# ProPrj_OrcaSDVX.net
KiCad netlist of a schematic drawn in EasyEDA Pro
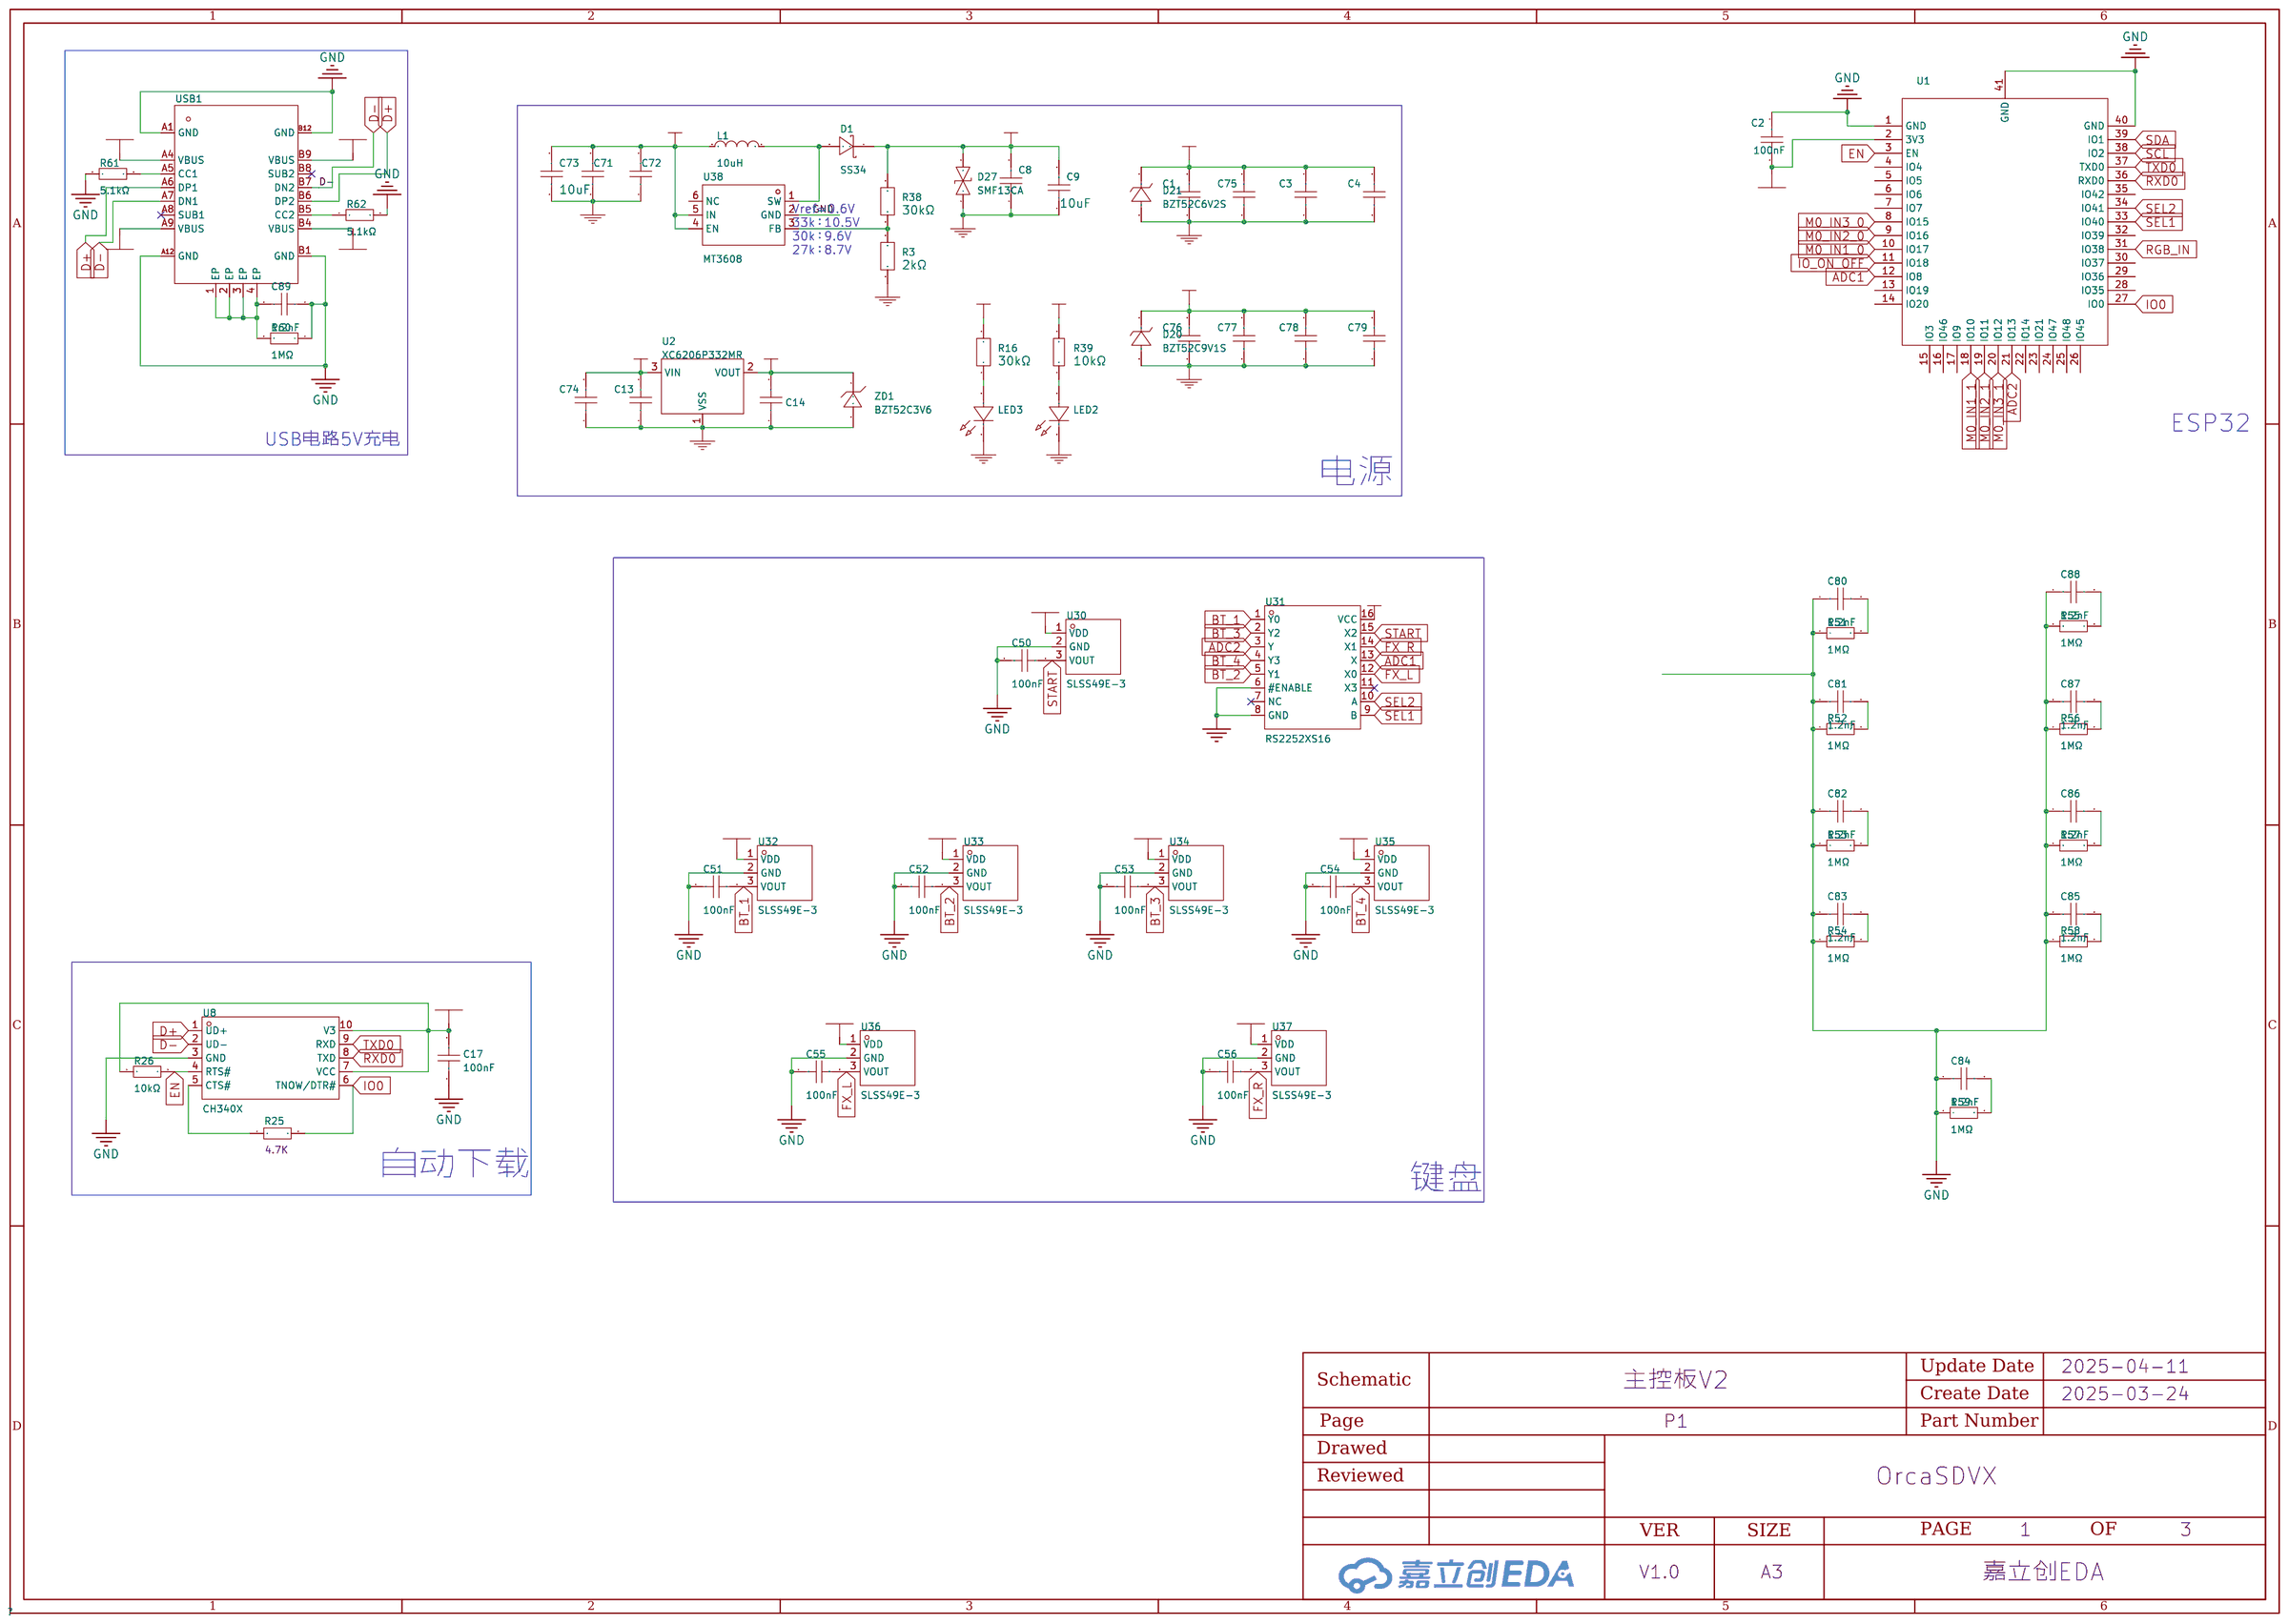
[diagram p0: P1]
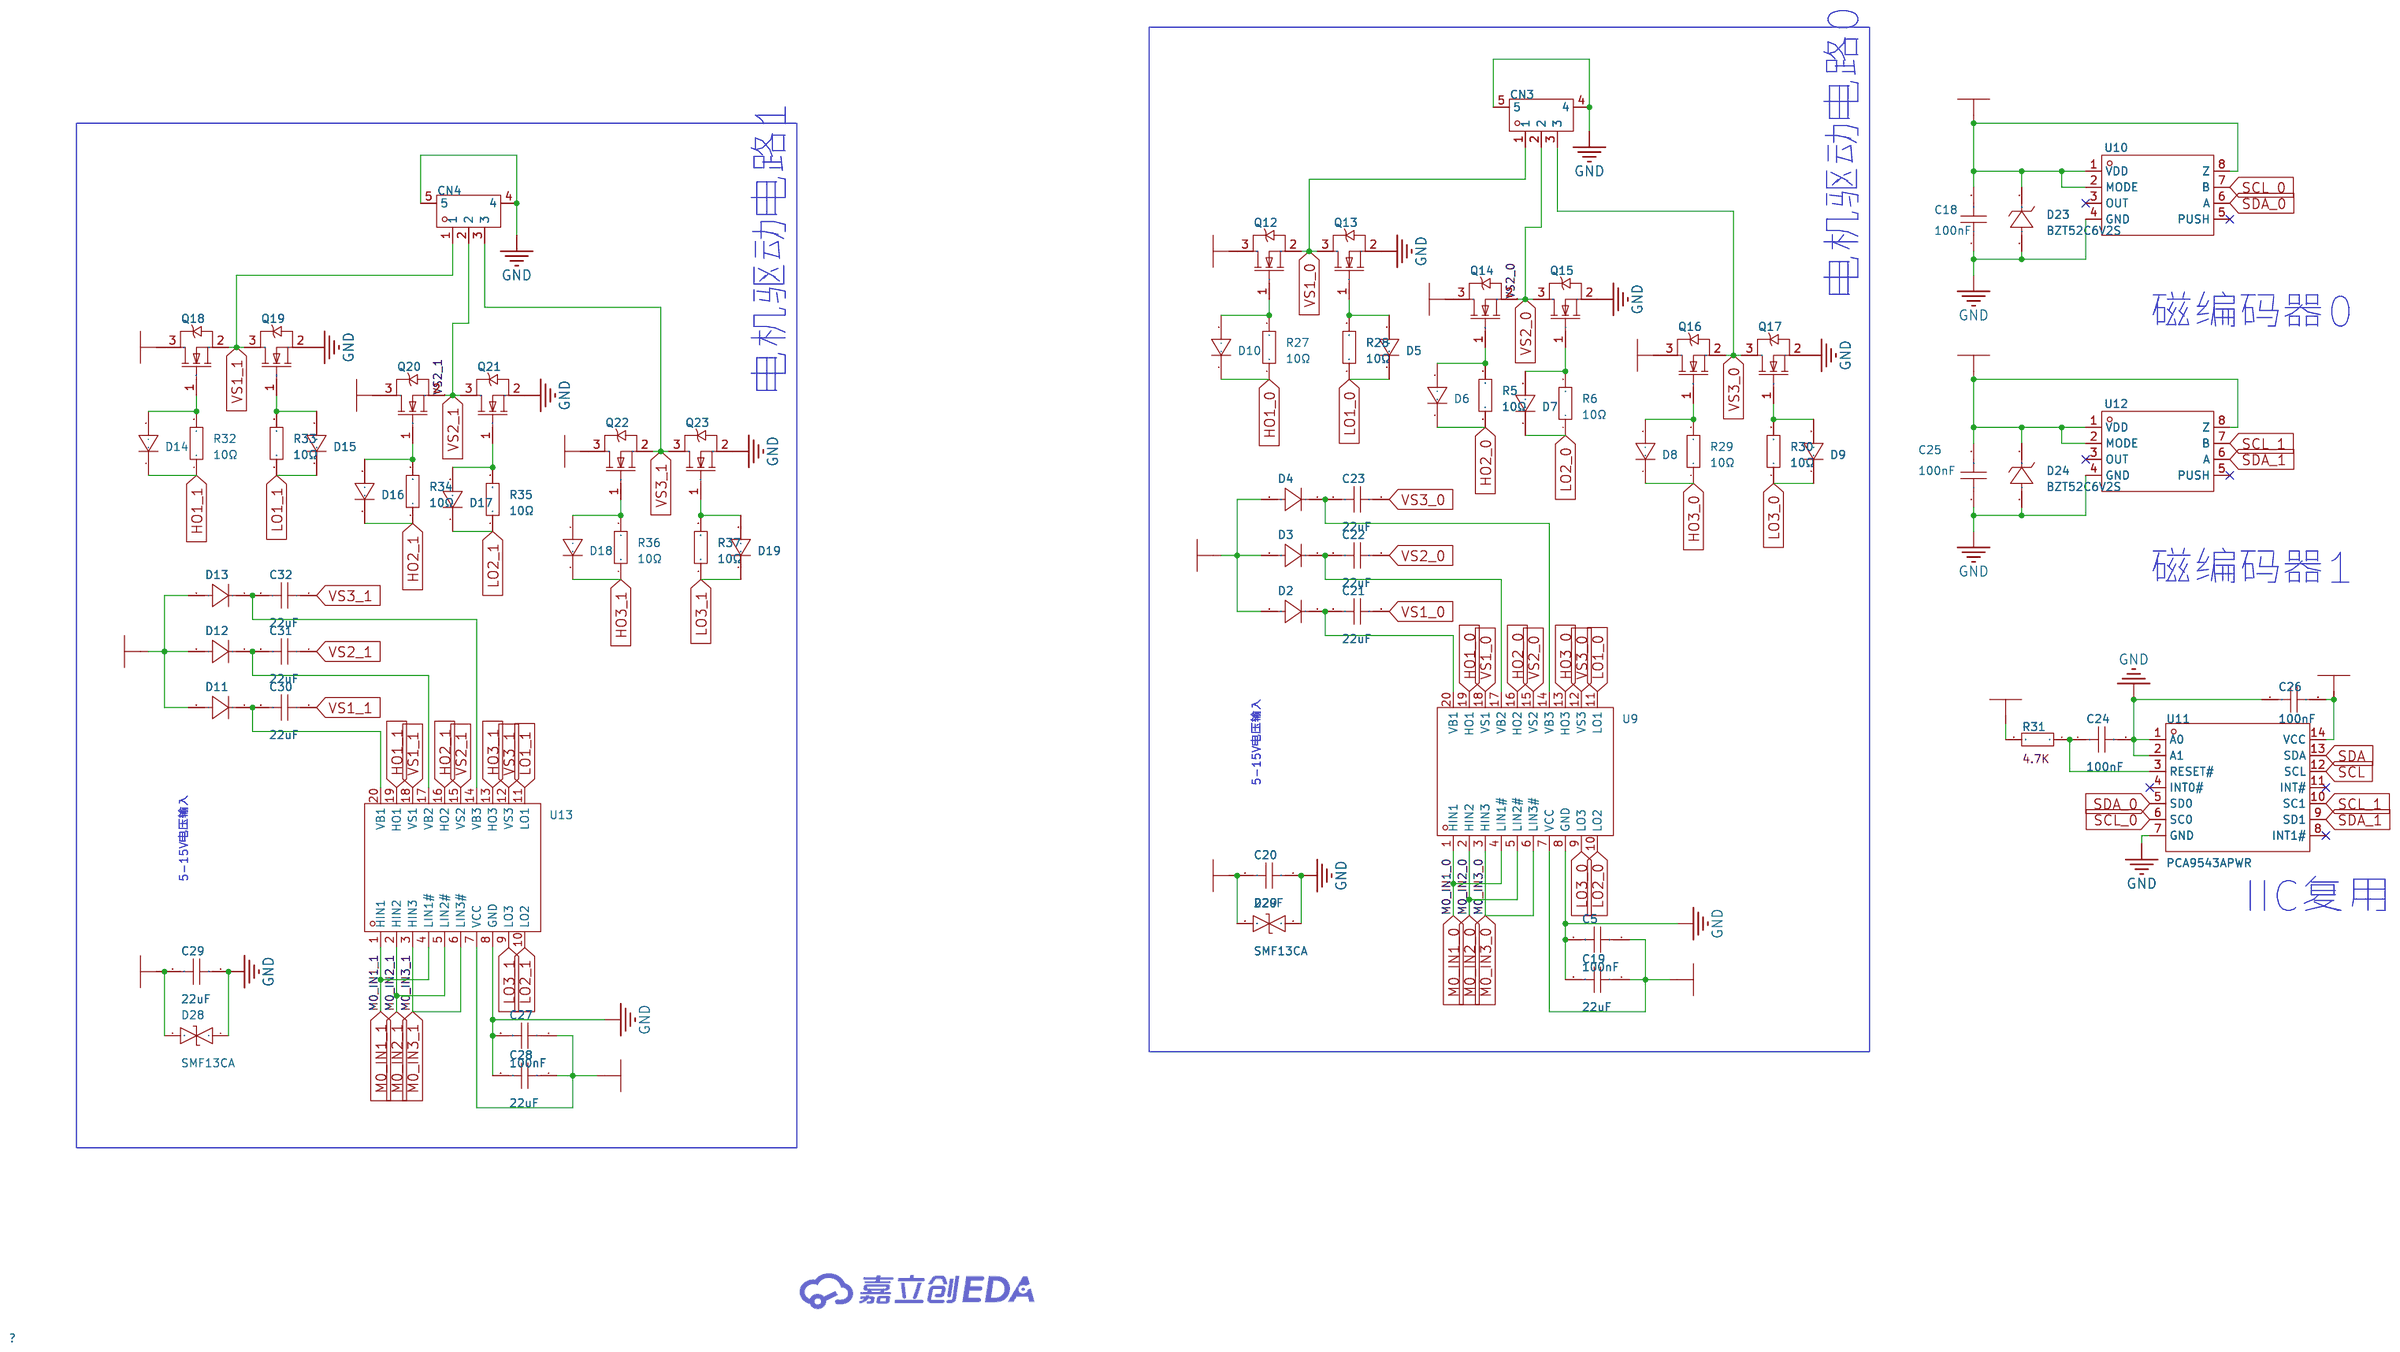
[diagram p1: 电机驱动电路]
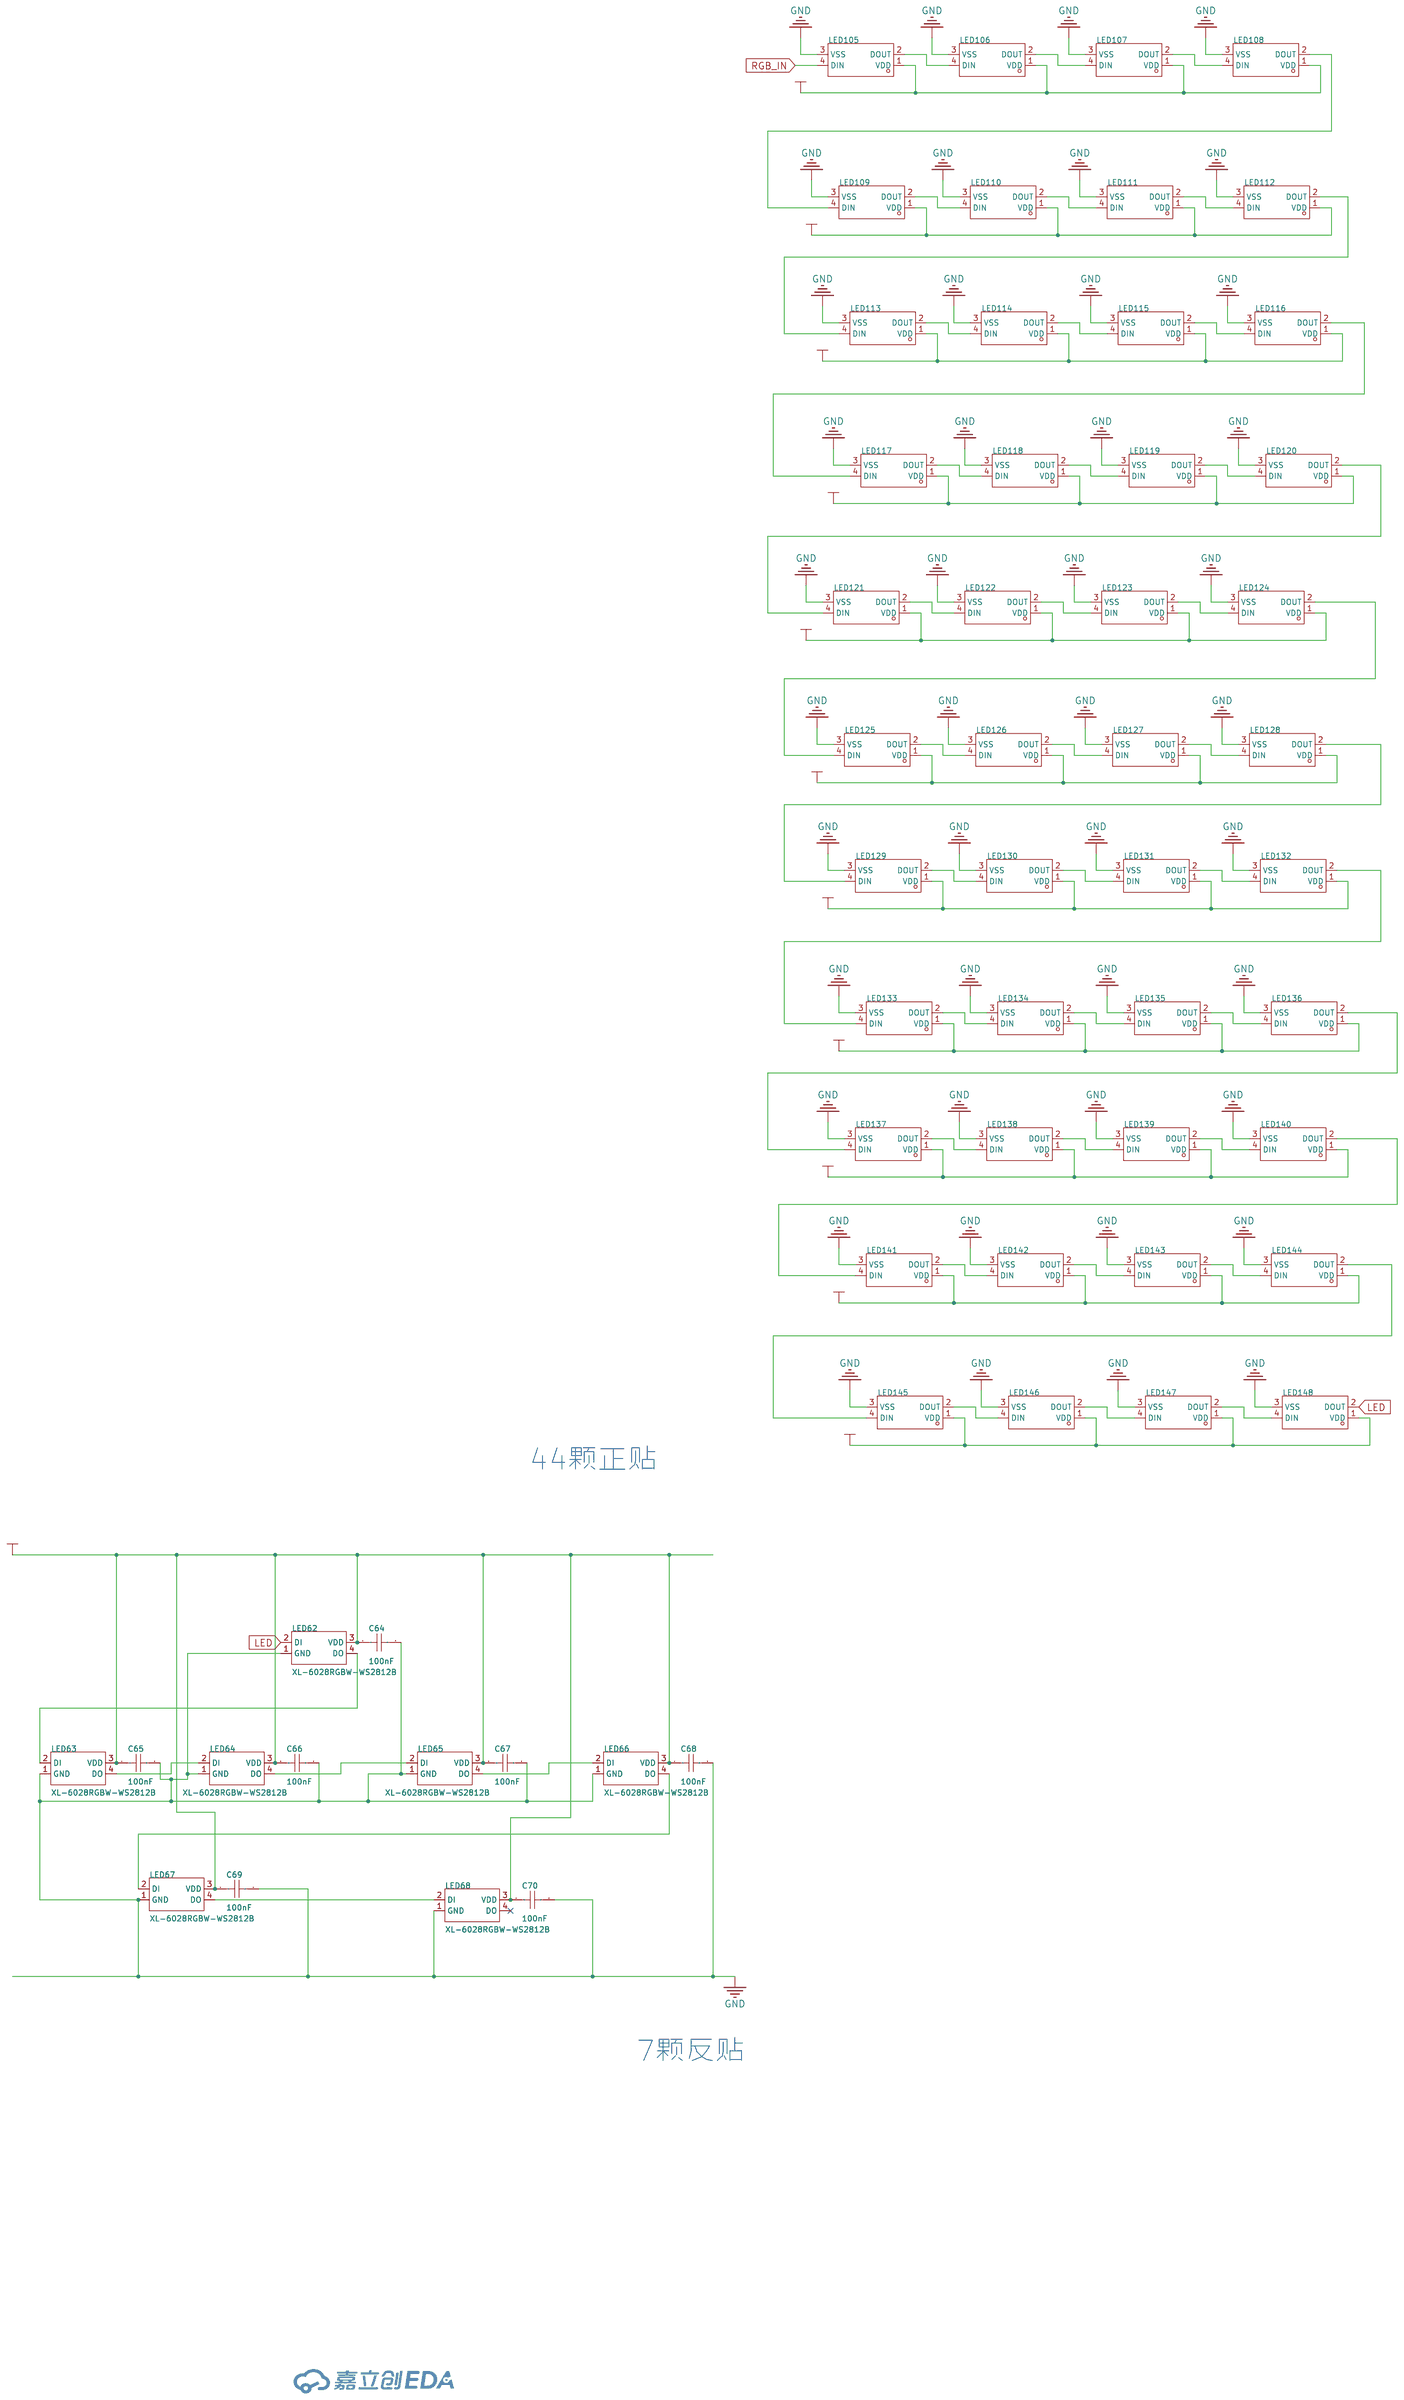
[diagram p2: 灯]

(export (version "E")
  (design (tool "Eeschema 10.0.6"))
  (components
    (comp (ref "C1") (value "100nF") (libsource (lib "easyedapro") (part "CC0603KRX7R9BB104")))
    (comp (ref "C2")
      (value "100nF")
      (footprint "easyedapro:C0603")
      (description "容值:100nF;精度:±10%;额定电压:50V;温度系数:X7R;")
      (fields
        (field (name "Manufacturer Part") "CC0603KRX7R9BB104")
        (field (name "Manufacturer") "YAGEO(国巨)")
      )
      (libsource (lib "") (part "CC0603KRX7R9BB104_1"))
    )
    (comp (ref "C3") (value "100nF") (libsource (lib "easyedapro") (part "CC0603KRX7R9BB104")))
    (comp (ref "C4") (value "100nF") (libsource (lib "easyedapro") (part "CC0603KRX7R9BB104")))
    (comp (ref "C8") (value "100nF") (libsource (lib "easyedapro") (part "CC0603KRX7R9BB104")))
    (comp (ref "C9") (value "10uF") (libsource (lib "easyedapro") (part "CL21A106KAYNNNE")))
    (comp (ref "C13") (value "100nF") (libsource (lib "easyedapro") (part "CC0603KRX7R9BB104")))
    (comp (ref "C14") (value "100nF") (libsource (lib "easyedapro") (part "CC0603KRX7R9BB104")))
    (comp (ref "C17")
      (value "100nF")
      (footprint "easyedapro:C0603")
      (description "容值:100nF;精度:±10%;额定电压:50V;温度系数:X7R;")
      (fields
        (field (name "Manufacturer Part") "CC0603KRX7R9BB104")
        (field (name "Manufacturer") "YAGEO(国巨)")
      )
      (libsource (lib "") (part "CC0603KRX7R9BB104_1"))
    )
    (comp (ref "C50")
      (value "100nF")
      (footprint "easyedapro:C0603")
      (description "容值:100nF;精度:±10%;额定电压:50V;温度系数:X7R;")
      (fields
        (field (name "Manufacturer Part") "CGA0603X7R104K500JT")
        (field (name "Manufacturer") "HRE(芯声)")
      )
      (libsource (lib "easyedapro") (part "CGA0603X7R104K500JT"))
    )
    (comp (ref "C51")
      (value "100nF")
      (footprint "easyedapro:C0603")
      (description "容值:100nF;精度:±10%;额定电压:50V;温度系数:X7R;")
      (fields
        (field (name "Manufacturer Part") "CGA0603X7R104K500JT")
        (field (name "Manufacturer") "HRE(芯声)")
      )
      (libsource (lib "easyedapro") (part "CGA0603X7R104K500JT"))
    )
    (comp (ref "C52")
      (value "100nF")
      (footprint "easyedapro:C0603")
      (description "容值:100nF;精度:±10%;额定电压:50V;温度系数:X7R;")
      (fields
        (field (name "Manufacturer Part") "CGA0603X7R104K500JT")
        (field (name "Manufacturer") "HRE(芯声)")
      )
      (libsource (lib "easyedapro") (part "CGA0603X7R104K500JT"))
    )
    (comp (ref "C53")
      (value "100nF")
      (footprint "easyedapro:C0603")
      (description "容值:100nF;精度:±10%;额定电压:50V;温度系数:X7R;")
      (fields
        (field (name "Manufacturer Part") "CGA0603X7R104K500JT")
        (field (name "Manufacturer") "HRE(芯声)")
      )
      (libsource (lib "easyedapro") (part "CGA0603X7R104K500JT"))
    )
    (comp (ref "C54")
      (value "100nF")
      (footprint "easyedapro:C0603")
      (description "容值:100nF;精度:±10%;额定电压:50V;温度系数:X7R;")
      (fields
        (field (name "Manufacturer Part") "CGA0603X7R104K500JT")
        (field (name "Manufacturer") "HRE(芯声)")
      )
      (libsource (lib "easyedapro") (part "CGA0603X7R104K500JT"))
    )
    (comp (ref "C55")
      (value "100nF")
      (footprint "easyedapro:C0603")
      (description "容值:100nF;精度:±10%;额定电压:50V;温度系数:X7R;")
      (fields
        (field (name "Manufacturer Part") "CGA0603X7R104K500JT")
        (field (name "Manufacturer") "HRE(芯声)")
      )
      (libsource (lib "easyedapro") (part "CGA0603X7R104K500JT"))
    )
    (comp (ref "C56")
      (value "100nF")
      (footprint "easyedapro:C0603")
      (description "容值:100nF;精度:±10%;额定电压:50V;温度系数:X7R;")
      (fields
        (field (name "Manufacturer Part") "CGA0603X7R104K500JT")
        (field (name "Manufacturer") "HRE(芯声)")
      )
      (libsource (lib "easyedapro") (part "CGA0603X7R104K500JT"))
    )
    (comp (ref "C71") (value "100nF") (libsource (lib "easyedapro") (part "CC0603KRX7R9BB104")))
    (comp (ref "C72") (value "100nF") (libsource (lib "easyedapro") (part "CC0603KRX7R9BB104")))
    (comp (ref "C73")
      (value "10uF")
      (fields
        (field (name "Manufacturer Part") "CL10A106MA8NRNC")
        (field (name "Manufacturer") "SAMSUNG(三星)")
      )
      (libsource (lib "easyedapro") (part "CL21A106KAYNNNE"))
    )
    (comp (ref "C74") (value "100nF") (libsource (lib "easyedapro") (part "CC0603KRX7R9BB104")))
    (comp (ref "C75") (value "100nF") (libsource (lib "easyedapro") (part "CC0603KRX7R9BB104")))
    (comp (ref "C76") (value "100nF") (libsource (lib "easyedapro") (part "CC0603KRX7R9BB104")))
    (comp (ref "C77") (value "100nF") (libsource (lib "easyedapro") (part "CC0603KRX7R9BB104")))
    (comp (ref "C78") (value "100nF") (libsource (lib "easyedapro") (part "CC0603KRX7R9BB104")))
    (comp (ref "C79") (value "100nF") (libsource (lib "easyedapro") (part "CC0603KRX7R9BB104")))
    (comp (ref "C80")
      (value "1.2nF")
      (footprint "easyedapro:C1210")
      (description "容值:1.2nF;精度:±5%;额定电压:1kV;温度系数:C0G;")
      (fields (field (name "Manufacturer Part") "FV32N122J102EEG") (field (name "Manufacturer") "PSA(信昌电陶)"))
      (libsource (lib "easyedapro") (part "FV32N122J102EEG"))
    )
    (comp (ref "C81")
      (value "1.2nF")
      (footprint "easyedapro:C1210")
      (description "容值:1.2nF;精度:±5%;额定电压:1kV;温度系数:C0G;")
      (fields (field (name "Manufacturer Part") "FV32N122J102EEG") (field (name "Manufacturer") "PSA(信昌电陶)"))
      (libsource (lib "easyedapro") (part "FV32N122J102EEG"))
    )
    (comp (ref "C82")
      (value "1.2nF")
      (footprint "easyedapro:C1210")
      (description "容值:1.2nF;精度:±5%;额定电压:1kV;温度系数:C0G;")
      (fields (field (name "Manufacturer Part") "FV32N122J102EEG") (field (name "Manufacturer") "PSA(信昌电陶)"))
      (libsource (lib "easyedapro") (part "FV32N122J102EEG"))
    )
    (comp (ref "C83")
      (value "1.2nF")
      (footprint "easyedapro:C1210")
      (description "容值:1.2nF;精度:±5%;额定电压:1kV;温度系数:C0G;")
      (fields (field (name "Manufacturer Part") "FV32N122J102EEG") (field (name "Manufacturer") "PSA(信昌电陶)"))
      (libsource (lib "easyedapro") (part "FV32N122J102EEG"))
    )
    (comp (ref "C84")
      (value "1.2nF")
      (footprint "easyedapro:C1210")
      (description "容值:1.2nF;精度:±5%;额定电压:1kV;温度系数:C0G;")
      (fields (field (name "Manufacturer Part") "FV32N122J102EEG") (field (name "Manufacturer") "PSA(信昌电陶)"))
      (libsource (lib "easyedapro") (part "FV32N122J102EEG"))
    )
    (comp (ref "C85")
      (value "1.2nF")
      (footprint "easyedapro:C1210")
      (description "容值:1.2nF;精度:±5%;额定电压:1kV;温度系数:C0G;")
      (fields (field (name "Manufacturer Part") "FV32N122J102EEG") (field (name "Manufacturer") "PSA(信昌电陶)"))
      (libsource (lib "easyedapro") (part "FV32N122J102EEG"))
    )
    (comp (ref "C86")
      (value "1.2nF")
      (footprint "easyedapro:C1210")
      (description "容值:1.2nF;精度:±5%;额定电压:1kV;温度系数:C0G;")
      (fields (field (name "Manufacturer Part") "FV32N122J102EEG") (field (name "Manufacturer") "PSA(信昌电陶)"))
      (libsource (lib "easyedapro") (part "FV32N122J102EEG"))
    )
    (comp (ref "C87")
      (value "1.2nF")
      (footprint "easyedapro:C1210")
      (description "容值:1.2nF;精度:±5%;额定电压:1kV;温度系数:C0G;")
      (fields (field (name "Manufacturer Part") "FV32N122J102EEG") (field (name "Manufacturer") "PSA(信昌电陶)"))
      (libsource (lib "easyedapro") (part "FV32N122J102EEG"))
    )
    (comp (ref "C88")
      (value "1.2nF")
      (footprint "easyedapro:C1210")
      (description "容值:1.2nF;精度:±5%;额定电压:1kV;温度系数:C0G;")
      (fields (field (name "Manufacturer Part") "FV32N122J102EEG") (field (name "Manufacturer") "PSA(信昌电陶)"))
      (libsource (lib "easyedapro") (part "FV32N122J102EEG"))
    )
    (comp (ref "C89")
      (value "1.2nF")
      (footprint "easyedapro:C1210")
      (description "容值:1.2nF;精度:±5%;额定电压:1kV;温度系数:C0G;")
      (fields (field (name "Manufacturer Part") "FV32N122J102EEG") (field (name "Manufacturer") "PSA(信昌电陶)"))
      (libsource (lib "easyedapro") (part "FV32N122J102EEG"))
    )
    (comp (ref "D1")
      (value "SS34")
      (footprint "easyedapro:SMA_L4.3-W2.6-LS5.2-RD")
      (description "二极管配置:独立式;正向压降(Vf):550mV@3A;直流反向耐压(Vr):40V;整流电流:3A;")
      (fields (field (name "Manufacturer") "MDD(辰达半导体)"))
      (libsource (lib "easyedapro") (part "SS34_C8678"))
    )
    (comp (ref "D20")
      (value "BZT52C9V1S")
      (footprint "easyedapro:SOD-323_L1.7-W1.3-LS2.6-RD")
      (description "二极管配置:独立式;稳压值(标称值):9.1V;稳压值(范围):8.5V~9.6V;耗散功率(Pd):200mW;")
      (fields (field (name "Manufacturer") "宏嘉诚"))
      (libsource (lib "easyedapro") (part "BZT52C9V1S_C19077445"))
    )
    (comp (ref "D21")
      (value "BZT52C6V2S")
      (footprint "easyedapro:SOD-323_L1.7-W1.3-LS2.6-RD")
      (description "二极管配置:独立式;稳压值(标称值):6.2V;稳压值(范围):5.8V~6.2V;功率(Pd):200mW;")
      (fields (field (name "Manufacturer") "宏迦橙"))
      (libsource (lib "easyedapro") (part "BZT52C6V2S_C19077442"))
    )
    (comp (ref "D27")
      (value "SMF13CA")
      (footprint "easyedapro:SOD-123_L2.8-W1.8-LS3.7-BI-1")
      (description "极性:双向;反向截止电压(Vrwm):13V;钳位电压:21.5V;峰值脉冲电流(Ipp):9.3A;峰值脉冲功率(Ppp):200W;击穿电压:14.4V;")
      (fields (field (name "Manufacturer") "ElecSuper(静芯微)"))
      (libsource (lib "easyedapro") (part "SMF13CA_C5693166"))
    )
    (comp (ref "L1")
      (value "10uH")
      (footprint "easyedapro:IND-SMD_L3.0-W3.0_FTC303020D")
      (description "电感值:10uH;精度:±20%;额定电流:2.5A;饱和电流(Isat):3.8A;类型:一体成型电感;")
      (fields
        (field (name "Manufacturer Part") "FTC303020D100MBCA")
        (field (name "Manufacturer") "cjiang(长江微电)")
      )
      (libsource (lib "easyedapro") (part "FTC303020D100MBCA"))
    )
    (comp (ref "LED2") (value "XL-1608UGC-04") (libsource (lib "easyedapro") (part "XL-1608PGC-06")))
    (comp (ref "LED3") (value "XL-1608UGC-04") (libsource (lib "easyedapro") (part "XL-1608PGC-06")))
    (comp (ref "R3")
      (value "2kΩ")
      (fields (field (name "Manufacturer") "UNI-ROYAL(厚声)"))
      (libsource (lib "easyedapro") (part "1k"))
    )
    (comp (ref "R16")
      (value "30kΩ")
      (fields (field (name "Manufacturer") "UNI-ROYAL(厚声)"))
      (libsource (lib "easyedapro") (part "1k"))
    )
    (comp (ref "R25")
      (value "~")
      (footprint "easyedapro:R0603")
      (description "4.7K")
      (fields
        (field (name "Manufacturer Part") "0603WAF4701T5E")
        (field (name "Manufacturer") "UNI-ROYAL(厚声)")
      )
      (libsource (lib "easyedapro") (part "0603WAF4701T5E"))
    )
    (comp (ref "R26")
      (value "10kΩ")
      (footprint "easyedapro:R0603")
      (description "电阻类型:厚膜电阻;阻值:10kΩ;精度:±1%;功率:1/10W;温度系数:±100ppm/;最大工作电压:75V;工作温度范围:-55~+155;")
      (fields
        (field (name "Manufacturer Part") "0603WAF1002T5E")
        (field (name "Manufacturer") "UNI-ROYAL(厚声)")
      )
      (libsource (lib "easyedapro") (part "0603WAF1002T5E"))
    )
    (comp (ref "R38")
      (value "30kΩ")
      (fields (field (name "Manufacturer") "UNI-ROYAL(厚声)"))
      (libsource (lib "easyedapro") (part "1k"))
    )
    (comp (ref "R39")
      (value "10kΩ")
      (fields (field (name "Manufacturer") "YAGEO(国巨)"))
      (libsource (lib "easyedapro") (part "RC0603FR-0710KL"))
    )
    (comp (ref "R51")
      (value "1MΩ")
      (footprint "easyedapro:R2512")
      (description "电阻类型:厚膜电阻;阻值:1MΩ;精度:±1%;功率:1W;最大工作电压:800V;")
      (fields
        (field (name "Manufacturer Part") "HR2512F1M00E04Z")
        (field (name "Manufacturer") "EVER OHMS(天二科技)")
      )
      (libsource (lib "easyedapro") (part "HR2512F1ME04"))
    )
    (comp (ref "R52")
      (value "1MΩ")
      (footprint "easyedapro:R2512")
      (description "电阻类型:厚膜电阻;阻值:1MΩ;精度:±1%;功率:1W;最大工作电压:800V;")
      (fields
        (field (name "Manufacturer Part") "HR2512F1M00E04Z")
        (field (name "Manufacturer") "EVER OHMS(天二科技)")
      )
      (libsource (lib "easyedapro") (part "HR2512F1ME04"))
    )
    (comp (ref "R53")
      (value "1MΩ")
      (footprint "easyedapro:R2512")
      (description "电阻类型:厚膜电阻;阻值:1MΩ;精度:±1%;功率:1W;最大工作电压:800V;")
      (fields
        (field (name "Manufacturer Part") "HR2512F1M00E04Z")
        (field (name "Manufacturer") "EVER OHMS(天二科技)")
      )
      (libsource (lib "easyedapro") (part "HR2512F1ME04"))
    )
    (comp (ref "R54")
      (value "1MΩ")
      (footprint "easyedapro:R2512")
      (description "电阻类型:厚膜电阻;阻值:1MΩ;精度:±1%;功率:1W;最大工作电压:800V;")
      (fields
        (field (name "Manufacturer Part") "HR2512F1M00E04Z")
        (field (name "Manufacturer") "EVER OHMS(天二科技)")
      )
      (libsource (lib "easyedapro") (part "HR2512F1ME04"))
    )
    (comp (ref "R55")
      (value "1MΩ")
      (footprint "easyedapro:R2512")
      (description "电阻类型:厚膜电阻;阻值:1MΩ;精度:±1%;功率:1W;最大工作电压:800V;")
      (fields
        (field (name "Manufacturer Part") "HR2512F1M00E04Z")
        (field (name "Manufacturer") "EVER OHMS(天二科技)")
      )
      (libsource (lib "easyedapro") (part "HR2512F1ME04"))
    )
    (comp (ref "R56")
      (value "1MΩ")
      (footprint "easyedapro:R2512")
      (description "电阻类型:厚膜电阻;阻值:1MΩ;精度:±1%;功率:1W;最大工作电压:800V;")
      (fields
        (field (name "Manufacturer Part") "HR2512F1M00E04Z")
        (field (name "Manufacturer") "EVER OHMS(天二科技)")
      )
      (libsource (lib "easyedapro") (part "HR2512F1ME04"))
    )
    (comp (ref "R57")
      (value "1MΩ")
      (footprint "easyedapro:R2512")
      (description "电阻类型:厚膜电阻;阻值:1MΩ;精度:±1%;功率:1W;最大工作电压:800V;")
      (fields
        (field (name "Manufacturer Part") "HR2512F1M00E04Z")
        (field (name "Manufacturer") "EVER OHMS(天二科技)")
      )
      (libsource (lib "easyedapro") (part "HR2512F1ME04"))
    )
    (comp (ref "R58")
      (value "1MΩ")
      (footprint "easyedapro:R2512")
      (description "电阻类型:厚膜电阻;阻值:1MΩ;精度:±1%;功率:1W;最大工作电压:800V;")
      (fields
        (field (name "Manufacturer Part") "HR2512F1M00E04Z")
        (field (name "Manufacturer") "EVER OHMS(天二科技)")
      )
      (libsource (lib "easyedapro") (part "HR2512F1ME04"))
    )
    (comp (ref "R59")
      (value "1MΩ")
      (footprint "easyedapro:R2512")
      (description "电阻类型:厚膜电阻;阻值:1MΩ;精度:±1%;功率:1W;最大工作电压:800V;")
      (fields
        (field (name "Manufacturer Part") "HR2512F1M00E04Z")
        (field (name "Manufacturer") "EVER OHMS(天二科技)")
      )
      (libsource (lib "easyedapro") (part "HR2512F1ME04"))
    )
    (comp (ref "R60")
      (value "1MΩ")
      (footprint "easyedapro:R2512")
      (description "电阻类型:厚膜电阻;阻值:1MΩ;精度:±1%;功率:1W;最大工作电压:800V;")
      (fields
        (field (name "Manufacturer Part") "HR2512F1M00E04Z")
        (field (name "Manufacturer") "EVER OHMS(天二科技)")
      )
      (libsource (lib "easyedapro") (part "HR2512F1ME04"))
    )
    (comp (ref "R61")
      (value "5.1kΩ")
      (footprint "easyedapro:R0603")
      (description "电阻类型:厚膜电阻;阻值:5.1kΩ;精度:±1%;功率:100mW;最大工作电压:75V;温度系数:±100ppm/°C;")
      (fields
        (field (name "Manufacturer Part") "0603WAF5101T5E")
        (field (name "Manufacturer") "UNI-ROYAL(厚声)")
      )
      (libsource (lib "easyedapro") (part "0603WAF5101T5E"))
    )
    (comp (ref "R62")
      (value "5.1kΩ")
      (footprint "easyedapro:R0603")
      (description "电阻类型:厚膜电阻;阻值:5.1kΩ;精度:±1%;功率:100mW;最大工作电压:75V;温度系数:±100ppm/°C;")
      (fields
        (field (name "Manufacturer Part") "0603WAF5101T5E")
        (field (name "Manufacturer") "UNI-ROYAL(厚声)")
      )
      (libsource (lib "easyedapro") (part "0603WAF5101T5E"))
    )
    (comp (ref "U1")
      (value "ESP32-S3-WROOM-1U-N16R8")
      (footprint "easyedapro:WIRELM-SMD_ESP32-S3-WROOM-1U")
      (fields (field (name "Manufacturer") "ESPRESSIF(乐鑫)"))
      (libsource (lib "easyedapro") (part "ESP32-S3-WROOM-1U-N8"))
    )
    (comp (ref "U2")
      (value "XC6206P332MR")
      (footprint "easyedapro:SOT-23-3_L2.9-W1.3-P1.90-LS2.4-BR")
      (description "输出类型:固定;最大输入电压:8V;输出电压:3.3V;最大输出电流:300mA;输出极性:正极;")
      (fields (field (name "Manufacturer") "HXY MOSFET(华轩阳电子)"))
      (libsource (lib "easyedapro") (part "XC6206P332MR_C5148692"))
    )
    (comp (ref "U8")
      (value "CH340X")
      (footprint "easyedapro:MSOP-10_L3.0-W3.0-P0.50-LS5.0-BL")
      (fields (field (name "Manufacturer") "WCH(南京沁恒)"))
      (libsource (lib "easyedapro") (part "CH340X"))
    )
    (comp (ref "U30")
      (value "SLSS49E-3")
      (footprint "easyedapro:SOT-23-3_L2.9-W1.6-P1.90-LS2.8-BR-CW")
      (fields (field (name "Manufacturer") "Slkor(萨科微)"))
      (libsource (lib "easyedapro") (part "SLSS49E-3"))
    )
    (comp (ref "U31")
      (value "RS2252XS16")
      (footprint "easyedapro:SOIC-16_L9.9-W3.9-P1.27-LS6.0-BL")
      (description "2通道4选1复用器")
      (fields (field (name "Manufacturer") "RUNIC(润石)"))
      (libsource (lib "easyedapro") (part "RS2252XS16"))
    )
    (comp (ref "U32")
      (value "SLSS49E-3")
      (footprint "easyedapro:SOT-23-3_L2.9-W1.6-P1.90-LS2.8-BR-CW")
      (fields (field (name "Manufacturer") "Slkor(萨科微)"))
      (libsource (lib "easyedapro") (part "SLSS49E-3"))
    )
    (comp (ref "U33")
      (value "SLSS49E-3")
      (footprint "easyedapro:SOT-23-3_L2.9-W1.6-P1.90-LS2.8-BR-CW")
      (fields (field (name "Manufacturer") "Slkor(萨科微)"))
      (libsource (lib "easyedapro") (part "SLSS49E-3"))
    )
    (comp (ref "U34")
      (value "SLSS49E-3")
      (footprint "easyedapro:SOT-23-3_L2.9-W1.6-P1.90-LS2.8-BR-CW")
      (fields (field (name "Manufacturer") "Slkor(萨科微)"))
      (libsource (lib "easyedapro") (part "SLSS49E-3"))
    )
    (comp (ref "U35")
      (value "SLSS49E-3")
      (footprint "easyedapro:SOT-23-3_L2.9-W1.6-P1.90-LS2.8-BR-CW")
      (fields (field (name "Manufacturer") "Slkor(萨科微)"))
      (libsource (lib "easyedapro") (part "SLSS49E-3"))
    )
    (comp (ref "U36")
      (value "SLSS49E-3")
      (footprint "easyedapro:SOT-23-3_L2.9-W1.6-P1.90-LS2.8-BR-CW")
      (fields (field (name "Manufacturer") "Slkor(萨科微)"))
      (libsource (lib "easyedapro") (part "SLSS49E-3"))
    )
    (comp (ref "U37")
      (value "SLSS49E-3")
      (footprint "easyedapro:SOT-23-3_L2.9-W1.6-P1.90-LS2.8-BR-CW")
      (fields (field (name "Manufacturer") "Slkor(萨科微)"))
      (libsource (lib "easyedapro") (part "SLSS49E-3"))
    )
    (comp (ref "U38")
      (value "MT3608")
      (footprint "easyedapro:SOT-23-6_L2.9-W1.6-P0.95-LS2.8-BL")
      (description "功能类型:升压型;输入电压:2V~24V;输出电压:28V;输出电流(最大值):-;")
      (fields (field (name "Manufacturer") "西安航天民芯"))
      (libsource (lib "easyedapro") (part "MT3608"))
    )
    (comp (ref "USB1")
      (value "~")
      (footprint "easyedapro:USB-C-SMD_KH-TYPE-C-16P")
      (description "连接器类型:Type-C;标准:-;公母:母座;触点数量:16;端口数量:1;安装方式:卧贴;额定电流 - 电源:3A;工作温度范围:-40~+85;")
      (fields
        (field (name "Manufacturer Part") "KH-TYPE-C-16P")
        (field (name "Manufacturer") "kinghelm(金航标)")
      )
      (libsource (lib "easyedapro") (part "KH-TYPE-C-16P"))
    )
    (comp (ref "ZD1")
      (value "BZT52C3V6")
      (footprint "easyedapro:SOD-123_L2.8-W1.8-LS3.7-RD")
      (description "二极管配置:独立式;稳压值(标称值):3.6V;稳压值(范围):3.4V~3.8V;功率:350mW;精度:-;")
      (fields (field (name "Manufacturer") "CJ(江苏长电/长晶)"))
      (libsource (lib "easyedapro") (part "BZT52C3V6_C2113"))
    )
    (comp (ref "C5")
      (value "100nF")
      (footprint "easyedapro:C0603")
      (description "容值:100nF;精度:±10%;额定电压:50V;温度系数:X7R;")
      (fields
        (field (name "Manufacturer Part") "CC0603KRX7R9BB104")
        (field (name "Manufacturer") "YAGEO(国巨)")
      )
      (libsource (lib "easyedapro") (part "CC0603KRX7R9BB104"))
    )
    (comp (ref "C18")
      (value "100nF")
      (footprint "easyedapro:C0603")
      (description "容值:100nF;精度:±10%;额定电压:50V;温度系数:X7R;")
      (fields
        (field (name "Manufacturer Part") "CC0603KRX7R9BB104")
        (field (name "Manufacturer") "YAGEO(国巨)")
      )
      (libsource (lib "easyedapro") (part "CC0603KRX7R9BB104"))
    )
    (comp (ref "C19")
      (value "22uF")
      (footprint "easyedapro:C0805")
      (description "容值:22uF;精度:±20%;额定电压:25V;温度系数:X5R;")
      (fields
        (field (name "Manufacturer Part") "CL21A226MAQNNNE")
        (field (name "Manufacturer") "SAMSUNG(三星)")
      )
      (libsource (lib "easyedapro") (part "CL21A226MAQNNNE"))
    )
    (comp (ref "C20")
      (value "22uF")
      (footprint "easyedapro:C0805")
      (description "容值:22uF;精度:±20%;额定电压:25V;温度系数:X5R;")
      (fields
        (field (name "Manufacturer Part") "CL21A226MAQNNNE")
        (field (name "Manufacturer") "SAMSUNG(三星)")
      )
      (libsource (lib "easyedapro") (part "CL21A226MAQNNNE"))
    )
    (comp (ref "C21")
      (value "22uF")
      (footprint "easyedapro:C0805")
      (description "容值:22uF;精度:±20%;额定电压:25V;温度系数:X5R;")
      (fields
        (field (name "Manufacturer Part") "CL21A226MAQNNNE")
        (field (name "Manufacturer") "SAMSUNG(三星)")
      )
      (libsource (lib "easyedapro") (part "CL21A226MAQNNNE"))
    )
    (comp (ref "C22")
      (value "22uF")
      (footprint "easyedapro:C0805")
      (description "容值:22uF;精度:±20%;额定电压:25V;温度系数:X5R;")
      (fields
        (field (name "Manufacturer Part") "CL21A226MAQNNNE")
        (field (name "Manufacturer") "SAMSUNG(三星)")
      )
      (libsource (lib "easyedapro") (part "CL21A226MAQNNNE"))
    )
    (comp (ref "C23")
      (value "22uF")
      (footprint "easyedapro:C0805")
      (description "容值:22uF;精度:±20%;额定电压:25V;温度系数:X5R;")
      (fields
        (field (name "Manufacturer Part") "CL21A226MAQNNNE")
        (field (name "Manufacturer") "SAMSUNG(三星)")
      )
      (libsource (lib "easyedapro") (part "CL21A226MAQNNNE"))
    )
    (comp (ref "C24")
      (value "100nF")
      (footprint "easyedapro:C0603")
      (description "容值:100nF;精度:±10%;额定电压:50V;温度系数:X7R;")
      (fields
        (field (name "Manufacturer Part") "CC0603KRX7R9BB104")
        (field (name "Manufacturer") "YAGEO(国巨)")
      )
      (libsource (lib "easyedapro") (part "CC0603KRX7R9BB104"))
    )
    (comp (ref "C25")
      (value "100nF")
      (footprint "easyedapro:C0603")
      (description "容值:100nF;精度:±10%;额定电压:50V;温度系数:X7R;")
      (fields
        (field (name "Manufacturer Part") "CC0603KRX7R9BB104")
        (field (name "Manufacturer") "YAGEO(国巨)")
      )
      (libsource (lib "easyedapro") (part "CC0603KRX7R9BB104"))
    )
    (comp (ref "C26")
      (value "100nF")
      (footprint "easyedapro:C0603")
      (description "容值:100nF;精度:±10%;额定电压:50V;温度系数:X7R;")
      (fields
        (field (name "Manufacturer Part") "CC0603KRX7R9BB104")
        (field (name "Manufacturer") "YAGEO(国巨)")
      )
      (libsource (lib "easyedapro") (part "CC0603KRX7R9BB104"))
    )
    (comp (ref "C27")
      (value "100nF")
      (footprint "easyedapro:C0603")
      (description "容值:100nF;精度:±10%;额定电压:50V;温度系数:X7R;")
      (fields
        (field (name "Manufacturer Part") "CC0603KRX7R9BB104")
        (field (name "Manufacturer") "YAGEO(国巨)")
      )
      (libsource (lib "easyedapro") (part "CC0603KRX7R9BB104"))
    )
    (comp (ref "C28")
      (value "22uF")
      (footprint "easyedapro:C0805")
      (description "容值:22uF;精度:±20%;额定电压:25V;温度系数:X5R;")
      (fields
        (field (name "Manufacturer Part") "CL21A226MAQNNNE")
        (field (name "Manufacturer") "SAMSUNG(三星)")
      )
      (libsource (lib "easyedapro") (part "CL21A226MAQNNNE"))
    )
    (comp (ref "C29")
      (value "22uF")
      (footprint "easyedapro:C0805")
      (description "容值:22uF;精度:±20%;额定电压:25V;温度系数:X5R;")
      (fields
        (field (name "Manufacturer Part") "CL21A226MAQNNNE")
        (field (name "Manufacturer") "SAMSUNG(三星)")
      )
      (libsource (lib "easyedapro") (part "CL21A226MAQNNNE"))
    )
    (comp (ref "C30")
      (value "22uF")
      (footprint "easyedapro:C0805")
      (description "容值:22uF;精度:±20%;额定电压:25V;温度系数:X5R;")
      (fields
        (field (name "Manufacturer Part") "CL21A226MAQNNNE")
        (field (name "Manufacturer") "SAMSUNG(三星)")
      )
      (libsource (lib "easyedapro") (part "CL21A226MAQNNNE"))
    )
    (comp (ref "C31")
      (value "22uF")
      (footprint "easyedapro:C0805")
      (description "容值:22uF;精度:±20%;额定电压:25V;温度系数:X5R;")
      (fields
        (field (name "Manufacturer Part") "CL21A226MAQNNNE")
        (field (name "Manufacturer") "SAMSUNG(三星)")
      )
      (libsource (lib "easyedapro") (part "CL21A226MAQNNNE"))
    )
    (comp (ref "C32")
      (value "22uF")
      (footprint "easyedapro:C0805")
      (description "容值:22uF;精度:±20%;额定电压:25V;温度系数:X5R;")
      (fields
        (field (name "Manufacturer Part") "CL21A226MAQNNNE")
        (field (name "Manufacturer") "SAMSUNG(三星)")
      )
      (libsource (lib "easyedapro") (part "CL21A226MAQNNNE"))
    )
    (comp (ref "CN3")
      (value "~")
      (footprint "easyedapro:CONN-SMD_X0800WRS-03HF-LPV01")
      (description "参考系列:-;间距:0.8mm;插针结构:1x3P;排数:1;每排PIN数:3;行距:-;公母:公型插针;安装方式:卧贴;额定电流:500mA;工作温度范围:-25~+85;")
      (fields
        (field (name "Manufacturer Part") "X0800WRS-03HF-LPV01")
        (field (name "Manufacturer") "XKBConnectivity(中国星坤)")
      )
      (libsource (lib "easyedapro") (part "X0800WRS-03HF-LPV01"))
    )
    (comp (ref "CN4")
      (value "~")
      (footprint "easyedapro:CONN-SMD_X0800WRS-03HF-LPV01")
      (description "参考系列:-;间距:0.8mm;插针结构:1x3P;排数:1;每排PIN数:3;行距:-;公母:公型插针;安装方式:卧贴;额定电流:500mA;工作温度范围:-25~+85;")
      (fields
        (field (name "Manufacturer Part") "X0800WRS-03HF-LPV01")
        (field (name "Manufacturer") "XKBConnectivity(中国星坤)")
      )
      (libsource (lib "easyedapro") (part "X0800WRS-03HF-LPV01"))
    )
    (comp (ref "D2")
      (value "~")
      (footprint "easyedapro:SOD-123FL_L2.7-W1.8-LS3.8-RD")
      (fields (field (name "Manufacturer Part") "FR107") (field (name "Manufacturer") "Slkor(萨科微)"))
      (libsource (lib "easyedapro") (part "FR107_C2760867"))
    )
    (comp (ref "D3")
      (value "~")
      (footprint "easyedapro:SOD-123FL_L2.7-W1.8-LS3.8-RD")
      (fields (field (name "Manufacturer Part") "FR107") (field (name "Manufacturer") "Slkor(萨科微)"))
      (libsource (lib "easyedapro") (part "FR107_C2760867"))
    )
    (comp (ref "D4")
      (value "~")
      (footprint "easyedapro:SOD-123FL_L2.7-W1.8-LS3.8-RD")
      (fields (field (name "Manufacturer Part") "FR107") (field (name "Manufacturer") "Slkor(萨科微)"))
      (libsource (lib "easyedapro") (part "FR107_C2760867"))
    )
    (comp (ref "D5")
      (value "~")
      (footprint "easyedapro:SOD-123F_L2.7-W1.6-LS3.8-RD")
      (fields (field (name "Manufacturer Part") "1N4148W") (field (name "Manufacturer") "ST(先科)"))
      (libsource (lib "easyedapro") (part "1N4148W_C81598"))
    )
    (comp (ref "D6")
      (value "~")
      (footprint "easyedapro:SOD-123F_L2.7-W1.6-LS3.8-RD")
      (fields (field (name "Manufacturer Part") "1N4148W") (field (name "Manufacturer") "ST(先科)"))
      (libsource (lib "easyedapro") (part "1N4148W_C81598"))
    )
    (comp (ref "D7")
      (value "~")
      (footprint "easyedapro:SOD-123F_L2.7-W1.6-LS3.8-RD")
      (fields (field (name "Manufacturer Part") "1N4148W") (field (name "Manufacturer") "ST(先科)"))
      (libsource (lib "easyedapro") (part "1N4148W_C81598"))
    )
    (comp (ref "D8")
      (value "~")
      (footprint "easyedapro:SOD-123F_L2.7-W1.6-LS3.8-RD")
      (fields (field (name "Manufacturer Part") "1N4148W") (field (name "Manufacturer") "ST(先科)"))
      (libsource (lib "easyedapro") (part "1N4148W_C81598"))
    )
    (comp (ref "D9")
      (value "~")
      (footprint "easyedapro:SOD-123F_L2.7-W1.6-LS3.8-RD")
      (fields (field (name "Manufacturer Part") "1N4148W") (field (name "Manufacturer") "ST(先科)"))
      (libsource (lib "easyedapro") (part "1N4148W_C81598"))
    )
    (comp (ref "D10")
      (value "~")
      (footprint "easyedapro:SOD-123F_L2.7-W1.6-LS3.8-RD")
      (fields (field (name "Manufacturer Part") "1N4148W") (field (name "Manufacturer") "ST(先科)"))
      (libsource (lib "easyedapro") (part "1N4148W_C81598"))
    )
    (comp (ref "D11")
      (value "~")
      (footprint "easyedapro:SOD-123FL_L2.7-W1.8-LS3.8-RD")
      (fields (field (name "Manufacturer Part") "FR107") (field (name "Manufacturer") "Slkor(萨科微)"))
      (libsource (lib "easyedapro") (part "FR107_C2760867"))
    )
    (comp (ref "D12")
      (value "~")
      (footprint "easyedapro:SOD-123FL_L2.7-W1.8-LS3.8-RD")
      (fields (field (name "Manufacturer Part") "FR107") (field (name "Manufacturer") "Slkor(萨科微)"))
      (libsource (lib "easyedapro") (part "FR107_C2760867"))
    )
    (comp (ref "D13")
      (value "~")
      (footprint "easyedapro:SOD-123FL_L2.7-W1.8-LS3.8-RD")
      (fields (field (name "Manufacturer Part") "FR107") (field (name "Manufacturer") "Slkor(萨科微)"))
      (libsource (lib "easyedapro") (part "FR107_C2760867"))
    )
    (comp (ref "D14")
      (value "~")
      (footprint "easyedapro:SOD-123F_L2.7-W1.6-LS3.8-RD")
      (fields (field (name "Manufacturer Part") "1N4148W") (field (name "Manufacturer") "ST(先科)"))
      (libsource (lib "easyedapro") (part "1N4148W_C81598"))
    )
    (comp (ref "D15")
      (value "~")
      (footprint "easyedapro:SOD-123F_L2.7-W1.6-LS3.8-RD")
      (fields (field (name "Manufacturer Part") "1N4148W") (field (name "Manufacturer") "ST(先科)"))
      (libsource (lib "easyedapro") (part "1N4148W_C81598"))
    )
    (comp (ref "D16")
      (value "~")
      (footprint "easyedapro:SOD-123F_L2.7-W1.6-LS3.8-RD")
      (fields (field (name "Manufacturer Part") "1N4148W") (field (name "Manufacturer") "ST(先科)"))
      (libsource (lib "easyedapro") (part "1N4148W_C81598"))
    )
    (comp (ref "D17")
      (value "~")
      (footprint "easyedapro:SOD-123F_L2.7-W1.6-LS3.8-RD")
      (fields (field (name "Manufacturer Part") "1N4148W") (field (name "Manufacturer") "ST(先科)"))
      (libsource (lib "easyedapro") (part "1N4148W_C81598"))
    )
    (comp (ref "D18")
      (value "~")
      (footprint "easyedapro:SOD-123F_L2.7-W1.6-LS3.8-RD")
      (fields (field (name "Manufacturer Part") "1N4148W") (field (name "Manufacturer") "ST(先科)"))
      (libsource (lib "easyedapro") (part "1N4148W_C81598"))
    )
    (comp (ref "D19")
      (value "~")
      (footprint "easyedapro:SOD-123F_L2.7-W1.6-LS3.8-RD")
      (fields (field (name "Manufacturer Part") "1N4148W") (field (name "Manufacturer") "ST(先科)"))
      (libsource (lib "easyedapro") (part "1N4148W_C81598"))
    )
    (comp (ref "D23")
      (value "BZT52C6V2S")
      (footprint "easyedapro:SOD-323_L1.7-W1.3-LS2.6-RD")
      (description "二极管配置:独立式;稳压值(标称值):6.2V;稳压值(范围):5.8V~6.2V;功率(Pd):200mW;")
      (fields (field (name "Manufacturer") "宏迦橙"))
      (libsource (lib "easyedapro") (part "BZT52C6V2S_C19077442"))
    )
    (comp (ref "D24")
      (value "BZT52C6V2S")
      (footprint "easyedapro:SOD-323_L1.7-W1.3-LS2.6-RD")
      (description "二极管配置:独立式;稳压值(标称值):6.2V;稳压值(范围):5.8V~6.2V;功率(Pd):200mW;")
      (fields (field (name "Manufacturer") "宏迦橙"))
      (libsource (lib "easyedapro") (part "BZT52C6V2S_C19077442"))
    )
    (comp (ref "D28")
      (value "SMF13CA")
      (footprint "easyedapro:SOD-123_L2.8-W1.8-LS3.7-BI-1")
      (description "极性:双向;反向截止电压(Vrwm):13V;钳位电压:21.5V;峰值脉冲电流(Ipp):9.3A;峰值脉冲功率(Ppp):200W;击穿电压:14.4V;")
      (fields (field (name "Manufacturer") "ElecSuper(静芯微)"))
      (libsource (lib "easyedapro") (part "SMF13CA_C5693166"))
    )
    (comp (ref "D29")
      (value "SMF13CA")
      (footprint "easyedapro:SOD-123_L2.8-W1.8-LS3.7-BI-1")
      (description "极性:双向;反向截止电压(Vrwm):13V;钳位电压:21.5V;峰值脉冲电流(Ipp):9.3A;峰值脉冲功率(Ppp):200W;击穿电压:14.4V;")
      (fields (field (name "Manufacturer") "ElecSuper(静芯微)"))
      (libsource (lib "easyedapro") (part "SMF13CA_C5693166"))
    )
    (comp (ref "Q12")
      (value "~")
      (footprint "easyedapro:SOT-23-3_L2.9-W1.3-P0.95-LS2.4-BR")
      (fields (field (name "Manufacturer Part") "AP2300") (field (name "Manufacturer") "ALLPOWER(铨力)"))
      (libsource (lib "easyedapro") (part "AP2300"))
    )
    (comp (ref "Q13")
      (value "~")
      (footprint "easyedapro:SOT-23-3_L2.9-W1.3-P0.95-LS2.4-BR")
      (fields (field (name "Manufacturer Part") "AP2300") (field (name "Manufacturer") "ALLPOWER(铨力)"))
      (libsource (lib "easyedapro") (part "AP2300"))
    )
    (comp (ref "Q14")
      (value "~")
      (footprint "easyedapro:SOT-23-3_L2.9-W1.3-P0.95-LS2.4-BR")
      (fields (field (name "Manufacturer Part") "AP2300") (field (name "Manufacturer") "ALLPOWER(铨力)"))
      (libsource (lib "easyedapro") (part "AP2300"))
    )
    (comp (ref "Q15")
      (value "~")
      (footprint "easyedapro:SOT-23-3_L2.9-W1.3-P0.95-LS2.4-BR")
      (fields (field (name "Manufacturer Part") "AP2300") (field (name "Manufacturer") "ALLPOWER(铨力)"))
      (libsource (lib "easyedapro") (part "AP2300"))
    )
    (comp (ref "Q16")
      (value "~")
      (footprint "easyedapro:SOT-23-3_L2.9-W1.3-P0.95-LS2.4-BR")
      (fields (field (name "Manufacturer Part") "AP2300") (field (name "Manufacturer") "ALLPOWER(铨力)"))
      (libsource (lib "easyedapro") (part "AP2300"))
    )
    (comp (ref "Q17")
      (value "~")
      (footprint "easyedapro:SOT-23-3_L2.9-W1.3-P0.95-LS2.4-BR")
      (fields (field (name "Manufacturer Part") "AP2300") (field (name "Manufacturer") "ALLPOWER(铨力)"))
      (libsource (lib "easyedapro") (part "AP2300"))
    )
    (comp (ref "Q18")
      (value "~")
      (footprint "easyedapro:SOT-23-3_L2.9-W1.3-P0.95-LS2.4-BR")
      (fields (field (name "Manufacturer Part") "AP2300") (field (name "Manufacturer") "ALLPOWER(铨力)"))
      (libsource (lib "easyedapro") (part "AP2300"))
    )
    (comp (ref "Q19")
      (value "~")
      (footprint "easyedapro:SOT-23-3_L2.9-W1.3-P0.95-LS2.4-BR")
      (fields (field (name "Manufacturer Part") "AP2300") (field (name "Manufacturer") "ALLPOWER(铨力)"))
      (libsource (lib "easyedapro") (part "AP2300"))
    )
    (comp (ref "Q20")
      (value "~")
      (footprint "easyedapro:SOT-23-3_L2.9-W1.3-P0.95-LS2.4-BR")
      (fields (field (name "Manufacturer Part") "AP2300") (field (name "Manufacturer") "ALLPOWER(铨力)"))
      (libsource (lib "easyedapro") (part "AP2300"))
    )
    (comp (ref "Q21")
      (value "~")
      (footprint "easyedapro:SOT-23-3_L2.9-W1.3-P0.95-LS2.4-BR")
      (fields (field (name "Manufacturer Part") "AP2300") (field (name "Manufacturer") "ALLPOWER(铨力)"))
      (libsource (lib "easyedapro") (part "AP2300"))
    )
    (comp (ref "Q22")
      (value "~")
      (footprint "easyedapro:SOT-23-3_L2.9-W1.3-P0.95-LS2.4-BR")
      (fields (field (name "Manufacturer Part") "AP2300") (field (name "Manufacturer") "ALLPOWER(铨力)"))
      (libsource (lib "easyedapro") (part "AP2300"))
    )
    (comp (ref "Q23")
      (value "~")
      (footprint "easyedapro:SOT-23-3_L2.9-W1.3-P0.95-LS2.4-BR")
      (fields (field (name "Manufacturer Part") "AP2300") (field (name "Manufacturer") "ALLPOWER(铨力)"))
      (libsource (lib "easyedapro") (part "AP2300"))
    )
    (comp (ref "R5")
      (value "10Ω")
      (footprint "easyedapro:R0603")
      (description "电阻类型:厚膜电阻;阻值:10Ω;精度:±1%;功率:1/10W;温度系数:±400ppm/;最大工作电压:75V;工作温度范围:-55~+155;")
      (fields
        (field (name "Manufacturer Part") "0603WAF100JT5E")
        (field (name "Manufacturer") "UNI-ROYAL(厚声)")
      )
      (libsource (lib "easyedapro") (part "0603WAF100JT5E"))
    )
    (comp (ref "R6")
      (value "10Ω")
      (footprint "easyedapro:R0603")
      (description "电阻类型:厚膜电阻;阻值:10Ω;精度:±1%;功率:1/10W;温度系数:±400ppm/;最大工作电压:75V;工作温度范围:-55~+155;")
      (fields
        (field (name "Manufacturer Part") "0603WAF100JT5E")
        (field (name "Manufacturer") "UNI-ROYAL(厚声)")
      )
      (libsource (lib "easyedapro") (part "0603WAF100JT5E"))
    )
    (comp (ref "R27")
      (value "10Ω")
      (footprint "easyedapro:R0603")
      (description "电阻类型:厚膜电阻;阻值:10Ω;精度:±1%;功率:1/10W;温度系数:±400ppm/;最大工作电压:75V;工作温度范围:-55~+155;")
      (fields
        (field (name "Manufacturer Part") "0603WAF100JT5E")
        (field (name "Manufacturer") "UNI-ROYAL(厚声)")
      )
      (libsource (lib "easyedapro") (part "0603WAF100JT5E"))
    )
    (comp (ref "R28")
      (value "10Ω")
      (footprint "easyedapro:R0603")
      (description "电阻类型:厚膜电阻;阻值:10Ω;精度:±1%;功率:1/10W;温度系数:±400ppm/;最大工作电压:75V;工作温度范围:-55~+155;")
      (fields
        (field (name "Manufacturer Part") "0603WAF100JT5E")
        (field (name "Manufacturer") "UNI-ROYAL(厚声)")
      )
      (libsource (lib "easyedapro") (part "0603WAF100JT5E"))
    )
    (comp (ref "R29")
      (value "10Ω")
      (footprint "easyedapro:R0603")
      (description "电阻类型:厚膜电阻;阻值:10Ω;精度:±1%;功率:1/10W;温度系数:±400ppm/;最大工作电压:75V;工作温度范围:-55~+155;")
      (fields
        (field (name "Manufacturer Part") "0603WAF100JT5E")
        (field (name "Manufacturer") "UNI-ROYAL(厚声)")
      )
      (libsource (lib "easyedapro") (part "0603WAF100JT5E"))
    )
    (comp (ref "R30")
      (value "10Ω")
      (footprint "easyedapro:R0603")
      (description "电阻类型:厚膜电阻;阻值:10Ω;精度:±1%;功率:1/10W;温度系数:±400ppm/;最大工作电压:75V;工作温度范围:-55~+155;")
      (fields
        (field (name "Manufacturer Part") "0603WAF100JT5E")
        (field (name "Manufacturer") "UNI-ROYAL(厚声)")
      )
      (libsource (lib "easyedapro") (part "0603WAF100JT5E"))
    )
    (comp (ref "R31")
      (value "~")
      (footprint "easyedapro:R0603")
      (description "4.7K")
      (fields
        (field (name "Manufacturer Part") "0603WAF4701T5E")
        (field (name "Manufacturer") "UNI-ROYAL(厚声)")
      )
      (libsource (lib "easyedapro") (part "0603WAF4701T5E"))
    )
    (comp (ref "R32")
      (value "10Ω")
      (footprint "easyedapro:R0603")
      (description "电阻类型:厚膜电阻;阻值:10Ω;精度:±1%;功率:1/10W;温度系数:±400ppm/;最大工作电压:75V;工作温度范围:-55~+155;")
      (fields
        (field (name "Manufacturer Part") "0603WAF100JT5E")
        (field (name "Manufacturer") "UNI-ROYAL(厚声)")
      )
      (libsource (lib "easyedapro") (part "0603WAF100JT5E"))
    )
    (comp (ref "R33")
      (value "10Ω")
      (footprint "easyedapro:R0603")
      (description "电阻类型:厚膜电阻;阻值:10Ω;精度:±1%;功率:1/10W;温度系数:±400ppm/;最大工作电压:75V;工作温度范围:-55~+155;")
      (fields
        (field (name "Manufacturer Part") "0603WAF100JT5E")
        (field (name "Manufacturer") "UNI-ROYAL(厚声)")
      )
      (libsource (lib "easyedapro") (part "0603WAF100JT5E"))
    )
    (comp (ref "R34")
      (value "10Ω")
      (footprint "easyedapro:R0603")
      (description "电阻类型:厚膜电阻;阻值:10Ω;精度:±1%;功率:1/10W;温度系数:±400ppm/;最大工作电压:75V;工作温度范围:-55~+155;")
      (fields
        (field (name "Manufacturer Part") "0603WAF100JT5E")
        (field (name "Manufacturer") "UNI-ROYAL(厚声)")
      )
      (libsource (lib "easyedapro") (part "0603WAF100JT5E"))
    )
    (comp (ref "R35")
      (value "10Ω")
      (footprint "easyedapro:R0603")
      (description "电阻类型:厚膜电阻;阻值:10Ω;精度:±1%;功率:1/10W;温度系数:±400ppm/;最大工作电压:75V;工作温度范围:-55~+155;")
      (fields
        (field (name "Manufacturer Part") "0603WAF100JT5E")
        (field (name "Manufacturer") "UNI-ROYAL(厚声)")
      )
      (libsource (lib "easyedapro") (part "0603WAF100JT5E"))
    )
    (comp (ref "R36")
      (value "10Ω")
      (footprint "easyedapro:R0603")
      (description "电阻类型:厚膜电阻;阻值:10Ω;精度:±1%;功率:1/10W;温度系数:±400ppm/;最大工作电压:75V;工作温度范围:-55~+155;")
      (fields
        (field (name "Manufacturer Part") "0603WAF100JT5E")
        (field (name "Manufacturer") "UNI-ROYAL(厚声)")
      )
      (libsource (lib "easyedapro") (part "0603WAF100JT5E"))
    )
    (comp (ref "R37")
      (value "10Ω")
      (footprint "easyedapro:R0603")
      (description "电阻类型:厚膜电阻;阻值:10Ω;精度:±1%;功率:1/10W;温度系数:±400ppm/;最大工作电压:75V;工作温度范围:-55~+155;")
      (fields
        (field (name "Manufacturer Part") "0603WAF100JT5E")
        (field (name "Manufacturer") "UNI-ROYAL(厚声)")
      )
      (libsource (lib "easyedapro") (part "0603WAF100JT5E"))
    )
    (comp (ref "U9")
      (value "~")
      (footprint "easyedapro:TSSOP-20_L6.5-W4.4-P0.65-LS6.4-BL")
      (description "EG2133是一款高性价比的三相半桥驱动芯片，配合六颗Nmos可以组成三相直流无刷电机驱动器。包装为管装。")
      (fields (field (name "Manufacturer Part") "EG2133") (field (name "Manufacturer") "EG(屹晶微)"))
      (libsource (lib "easyedapro") (part "EG2133"))
    )
    (comp (ref "U10")
      (value "~")
      (footprint "easyedapro:SOP-8_L4.9-W3.9-P1.27-LS6.0-BL")
      (description "磁性编码器 磁性编码开关 磁性角度检测IC 可编程磁性角度位置芯片")
      (fields (field (name "Manufacturer Part") "MT6701CT-STD") (field (name "Manufacturer") "MagnTek(麦歌恩)"))
      (libsource (lib "easyedapro") (part "MT6701CT-STD"))
    )
    (comp (ref "U11")
      (value "PCA9543APWR")
      (footprint "easyedapro:TSSOP-14_L5.0-W4.4-P0.65-LS6.4-BL")
      (description "PCA9543A 具有中断、复位和电压转换功能的 2 通道 2.3V 至 5.5V I2C/SMBus 开关")
      (fields (field (name "Manufacturer") "TI(德州仪器)"))
      (libsource (lib "easyedapro") (part "PCA9543APWR"))
    )
    (comp (ref "U12")
      (value "~")
      (footprint "easyedapro:SOP-8_L4.9-W3.9-P1.27-LS6.0-BL")
      (description "磁性编码器 磁性编码开关 磁性角度检测IC 可编程磁性角度位置芯片")
      (fields (field (name "Manufacturer Part") "MT6701CT-STD") (field (name "Manufacturer") "MagnTek(麦歌恩)"))
      (libsource (lib "easyedapro") (part "MT6701CT-STD"))
    )
    (comp (ref "U13")
      (value "~")
      (footprint "easyedapro:TSSOP-20_L6.5-W4.4-P0.65-LS6.4-BL")
      (description "EG2133是一款高性价比的三相半桥驱动芯片，配合六颗Nmos可以组成三相直流无刷电机驱动器。包装为管装。")
      (fields (field (name "Manufacturer Part") "EG2133") (field (name "Manufacturer") "EG(屹晶微)"))
      (libsource (lib "easyedapro") (part "EG2133"))
    )
    (comp (ref "C64")
      (value "100nF")
      (footprint "easyedapro:C0603")
      (description "容值:100nF;精度:±10%;额定电压:50V;温度系数:X7R;")
      (fields
        (field (name "Manufacturer Part") "CGA0603X7R104K500JT")
        (field (name "Manufacturer") "HRE(芯声)")
      )
      (libsource (lib "easyedapro") (part "CGA0603X7R104K500JT"))
    )
    (comp (ref "C65")
      (value "100nF")
      (footprint "easyedapro:C0603")
      (description "容值:100nF;精度:±10%;额定电压:50V;温度系数:X7R;")
      (fields
        (field (name "Manufacturer Part") "CGA0603X7R104K500JT")
        (field (name "Manufacturer") "HRE(芯声)")
      )
      (libsource (lib "easyedapro") (part "CGA0603X7R104K500JT"))
    )
    (comp (ref "C66")
      (value "100nF")
      (footprint "easyedapro:C0603")
      (description "容值:100nF;精度:±10%;额定电压:50V;温度系数:X7R;")
      (fields
        (field (name "Manufacturer Part") "CGA0603X7R104K500JT")
        (field (name "Manufacturer") "HRE(芯声)")
      )
      (libsource (lib "easyedapro") (part "CGA0603X7R104K500JT"))
    )
    (comp (ref "C67")
      (value "100nF")
      (footprint "easyedapro:C0603")
      (description "容值:100nF;精度:±10%;额定电压:50V;温度系数:X7R;")
      (fields
        (field (name "Manufacturer Part") "CGA0603X7R104K500JT")
        (field (name "Manufacturer") "HRE(芯声)")
      )
      (libsource (lib "easyedapro") (part "CGA0603X7R104K500JT"))
    )
    (comp (ref "C68")
      (value "100nF")
      (footprint "easyedapro:C0603")
      (description "容值:100nF;精度:±10%;额定电压:50V;温度系数:X7R;")
      (fields
        (field (name "Manufacturer Part") "CGA0603X7R104K500JT")
        (field (name "Manufacturer") "HRE(芯声)")
      )
      (libsource (lib "easyedapro") (part "CGA0603X7R104K500JT"))
    )
    (comp (ref "C69")
      (value "100nF")
      (footprint "easyedapro:C0603")
      (description "容值:100nF;精度:±10%;额定电压:50V;温度系数:X7R;")
      (fields
        (field (name "Manufacturer Part") "CGA0603X7R104K500JT")
        (field (name "Manufacturer") "HRE(芯声)")
      )
      (libsource (lib "easyedapro") (part "CGA0603X7R104K500JT"))
    )
    (comp (ref "C70")
      (value "100nF")
      (footprint "easyedapro:C0603")
      (description "容值:100nF;精度:±10%;额定电压:50V;温度系数:X7R;")
      (fields
        (field (name "Manufacturer Part") "CGA0603X7R104K500JT")
        (field (name "Manufacturer") "HRE(芯声)")
      )
      (libsource (lib "easyedapro") (part "CGA0603X7R104K500JT"))
    )
    (comp (ref "LED62")
      (value "XL-6028RGBW-WS2812B")
      (footprint "easyedapro:LED-SMD_4P-L3.2-W2.8-XL-6028RGBW-WS2812B")
      (description "6028幻彩雾状（ws2812b)")
      (fields (field (name "Manufacturer") "XINGLIGHT(成兴光)"))
      (libsource (lib "easyedapro") (part "XL-6028RGBW-WS2812B"))
    )
    (comp (ref "LED63")
      (value "XL-6028RGBW-WS2812B")
      (footprint "easyedapro:LED-SMD_4P-L3.2-W2.8-XL-6028RGBW-WS2812B")
      (description "6028幻彩雾状（ws2812b)")
      (fields (field (name "Manufacturer") "XINGLIGHT(成兴光)"))
      (libsource (lib "easyedapro") (part "XL-6028RGBW-WS2812B"))
    )
    (comp (ref "LED64")
      (value "XL-6028RGBW-WS2812B")
      (footprint "easyedapro:LED-SMD_4P-L3.2-W2.8-XL-6028RGBW-WS2812B")
      (description "6028幻彩雾状（ws2812b)")
      (fields (field (name "Manufacturer") "XINGLIGHT(成兴光)"))
      (libsource (lib "easyedapro") (part "XL-6028RGBW-WS2812B"))
    )
    (comp (ref "LED65")
      (value "XL-6028RGBW-WS2812B")
      (footprint "easyedapro:LED-SMD_4P-L3.2-W2.8-XL-6028RGBW-WS2812B")
      (description "6028幻彩雾状（ws2812b)")
      (fields (field (name "Manufacturer") "XINGLIGHT(成兴光)"))
      (libsource (lib "easyedapro") (part "XL-6028RGBW-WS2812B"))
    )
    (comp (ref "LED66")
      (value "XL-6028RGBW-WS2812B")
      (footprint "easyedapro:LED-SMD_4P-L3.2-W2.8-XL-6028RGBW-WS2812B")
      (description "6028幻彩雾状（ws2812b)")
      (fields (field (name "Manufacturer") "XINGLIGHT(成兴光)"))
      (libsource (lib "easyedapro") (part "XL-6028RGBW-WS2812B"))
    )
    (comp (ref "LED67")
      (value "XL-6028RGBW-WS2812B")
      (footprint "easyedapro:LED-SMD_4P-L3.2-W2.8-XL-6028RGBW-WS2812B")
      (description "6028幻彩雾状（ws2812b)")
      (fields (field (name "Manufacturer") "XINGLIGHT(成兴光)"))
      (libsource (lib "easyedapro") (part "XL-6028RGBW-WS2812B"))
    )
    (comp (ref "LED68")
      (value "XL-6028RGBW-WS2812B")
      (footprint "easyedapro:LED-SMD_4P-L3.2-W2.8-XL-6028RGBW-WS2812B")
      (description "6028幻彩雾状（ws2812b)")
      (fields (field (name "Manufacturer") "XINGLIGHT(成兴光)"))
      (libsource (lib "easyedapro") (part "XL-6028RGBW-WS2812B"))
    )
    (comp (ref "LED105")
      (value "WS2812B-Mini")
      (footprint "easyedapro:LED-SMD_4P-L3.5-W3.5-TL_WS2812B")
      (fields (field (name "Manufacturer") "worldsemi"))
      (libsource (lib "easyedapro") (part "WS2812B-MINI"))
    )
    (comp (ref "LED106")
      (value "WS2812B-Mini")
      (footprint "easyedapro:LED-SMD_4P-L3.5-W3.5-TL_WS2812B")
      (fields (field (name "Manufacturer") "worldsemi"))
      (libsource (lib "easyedapro") (part "WS2812B-MINI"))
    )
    (comp (ref "LED107")
      (value "WS2812B-Mini")
      (footprint "easyedapro:LED-SMD_4P-L3.5-W3.5-TL_WS2812B")
      (fields (field (name "Manufacturer") "worldsemi"))
      (libsource (lib "easyedapro") (part "WS2812B-MINI"))
    )
    (comp (ref "LED108")
      (value "WS2812B-Mini")
      (footprint "easyedapro:LED-SMD_4P-L3.5-W3.5-TL_WS2812B")
      (fields (field (name "Manufacturer") "worldsemi"))
      (libsource (lib "easyedapro") (part "WS2812B-MINI"))
    )
    (comp (ref "LED109")
      (value "WS2812B-Mini")
      (footprint "easyedapro:LED-SMD_4P-L3.5-W3.5-TL_WS2812B")
      (fields (field (name "Manufacturer") "worldsemi"))
      (libsource (lib "easyedapro") (part "WS2812B-MINI"))
    )
    (comp (ref "LED110")
      (value "WS2812B-Mini")
      (footprint "easyedapro:LED-SMD_4P-L3.5-W3.5-TL_WS2812B")
      (fields (field (name "Manufacturer") "worldsemi"))
      (libsource (lib "easyedapro") (part "WS2812B-MINI"))
    )
    (comp (ref "LED111")
      (value "WS2812B-Mini")
      (footprint "easyedapro:LED-SMD_4P-L3.5-W3.5-TL_WS2812B")
      (fields (field (name "Manufacturer") "worldsemi"))
      (libsource (lib "easyedapro") (part "WS2812B-MINI"))
    )
    (comp (ref "LED112")
      (value "WS2812B-Mini")
      (footprint "easyedapro:LED-SMD_4P-L3.5-W3.5-TL_WS2812B")
      (fields (field (name "Manufacturer") "worldsemi"))
      (libsource (lib "easyedapro") (part "WS2812B-MINI"))
    )
    (comp (ref "LED113")
      (value "WS2812B-Mini")
      (footprint "easyedapro:LED-SMD_4P-L3.5-W3.5-TL_WS2812B")
      (fields (field (name "Manufacturer") "worldsemi"))
      (libsource (lib "easyedapro") (part "WS2812B-MINI"))
    )
    (comp (ref "LED114")
      (value "WS2812B-Mini")
      (footprint "easyedapro:LED-SMD_4P-L3.5-W3.5-TL_WS2812B")
      (fields (field (name "Manufacturer") "worldsemi"))
      (libsource (lib "easyedapro") (part "WS2812B-MINI"))
    )
    (comp (ref "LED115")
      (value "WS2812B-Mini")
      (footprint "easyedapro:LED-SMD_4P-L3.5-W3.5-TL_WS2812B")
      (fields (field (name "Manufacturer") "worldsemi"))
      (libsource (lib "easyedapro") (part "WS2812B-MINI"))
    )
    (comp (ref "LED116")
      (value "WS2812B-Mini")
      (footprint "easyedapro:LED-SMD_4P-L3.5-W3.5-TL_WS2812B")
      (fields (field (name "Manufacturer") "worldsemi"))
      (libsource (lib "easyedapro") (part "WS2812B-MINI"))
    )
    (comp (ref "LED117")
      (value "WS2812B-Mini")
      (footprint "easyedapro:LED-SMD_4P-L3.5-W3.5-TL_WS2812B")
      (fields (field (name "Manufacturer") "worldsemi"))
      (libsource (lib "easyedapro") (part "WS2812B-MINI"))
    )
    (comp (ref "LED118")
      (value "WS2812B-Mini")
      (footprint "easyedapro:LED-SMD_4P-L3.5-W3.5-TL_WS2812B")
      (fields (field (name "Manufacturer") "worldsemi"))
      (libsource (lib "easyedapro") (part "WS2812B-MINI"))
    )
    (comp (ref "LED119")
      (value "WS2812B-Mini")
      (footprint "easyedapro:LED-SMD_4P-L3.5-W3.5-TL_WS2812B")
      (fields (field (name "Manufacturer") "worldsemi"))
      (libsource (lib "easyedapro") (part "WS2812B-MINI"))
    )
    (comp (ref "LED120")
      (value "WS2812B-Mini")
      (footprint "easyedapro:LED-SMD_4P-L3.5-W3.5-TL_WS2812B")
      (fields (field (name "Manufacturer") "worldsemi"))
      (libsource (lib "easyedapro") (part "WS2812B-MINI"))
    )
    (comp (ref "LED121")
      (value "WS2812B-Mini")
      (footprint "easyedapro:LED-SMD_4P-L3.5-W3.5-TL_WS2812B")
      (fields (field (name "Manufacturer") "worldsemi"))
      (libsource (lib "easyedapro") (part "WS2812B-MINI"))
    )
    (comp (ref "LED122")
      (value "WS2812B-Mini")
      (footprint "easyedapro:LED-SMD_4P-L3.5-W3.5-TL_WS2812B")
      (fields (field (name "Manufacturer") "worldsemi"))
      (libsource (lib "easyedapro") (part "WS2812B-MINI"))
    )
    (comp (ref "LED123")
      (value "WS2812B-Mini")
      (footprint "easyedapro:LED-SMD_4P-L3.5-W3.5-TL_WS2812B")
      (fields (field (name "Manufacturer") "worldsemi"))
      (libsource (lib "easyedapro") (part "WS2812B-MINI"))
    )
    (comp (ref "LED124")
      (value "WS2812B-Mini")
      (footprint "easyedapro:LED-SMD_4P-L3.5-W3.5-TL_WS2812B")
      (fields (field (name "Manufacturer") "worldsemi"))
      (libsource (lib "easyedapro") (part "WS2812B-MINI"))
    )
    (comp (ref "LED125")
      (value "WS2812B-Mini")
      (footprint "easyedapro:LED-SMD_4P-L3.5-W3.5-TL_WS2812B")
      (fields (field (name "Manufacturer") "worldsemi"))
      (libsource (lib "easyedapro") (part "WS2812B-MINI"))
    )
    (comp (ref "LED126")
      (value "WS2812B-Mini")
      (footprint "easyedapro:LED-SMD_4P-L3.5-W3.5-TL_WS2812B")
      (fields (field (name "Manufacturer") "worldsemi"))
      (libsource (lib "easyedapro") (part "WS2812B-MINI"))
    )
    (comp (ref "LED127")
      (value "WS2812B-Mini")
      (footprint "easyedapro:LED-SMD_4P-L3.5-W3.5-TL_WS2812B")
      (fields (field (name "Manufacturer") "worldsemi"))
      (libsource (lib "easyedapro") (part "WS2812B-MINI"))
    )
    (comp (ref "LED128")
      (value "WS2812B-Mini")
      (footprint "easyedapro:LED-SMD_4P-L3.5-W3.5-TL_WS2812B")
      (fields (field (name "Manufacturer") "worldsemi"))
      (libsource (lib "easyedapro") (part "WS2812B-MINI"))
    )
    (comp (ref "LED129")
      (value "WS2812B-Mini")
      (footprint "easyedapro:LED-SMD_4P-L3.5-W3.5-TL_WS2812B")
      (fields (field (name "Manufacturer") "worldsemi"))
      (libsource (lib "easyedapro") (part "WS2812B-MINI"))
    )
    (comp (ref "LED130")
      (value "WS2812B-Mini")
      (footprint "easyedapro:LED-SMD_4P-L3.5-W3.5-TL_WS2812B")
      (fields (field (name "Manufacturer") "worldsemi"))
      (libsource (lib "easyedapro") (part "WS2812B-MINI"))
    )
    (comp (ref "LED131")
      (value "WS2812B-Mini")
      (footprint "easyedapro:LED-SMD_4P-L3.5-W3.5-TL_WS2812B")
      (fields (field (name "Manufacturer") "worldsemi"))
      (libsource (lib "easyedapro") (part "WS2812B-MINI"))
    )
    (comp (ref "LED132")
      (value "WS2812B-Mini")
      (footprint "easyedapro:LED-SMD_4P-L3.5-W3.5-TL_WS2812B")
      (fields (field (name "Manufacturer") "worldsemi"))
      (libsource (lib "easyedapro") (part "WS2812B-MINI"))
    )
    (comp (ref "LED133")
      (value "WS2812B-Mini")
      (footprint "easyedapro:LED-SMD_4P-L3.5-W3.5-TL_WS2812B")
      (fields (field (name "Manufacturer") "worldsemi"))
      (libsource (lib "easyedapro") (part "WS2812B-MINI"))
    )
    (comp (ref "LED134")
      (value "WS2812B-Mini")
      (footprint "easyedapro:LED-SMD_4P-L3.5-W3.5-TL_WS2812B")
      (fields (field (name "Manufacturer") "worldsemi"))
      (libsource (lib "easyedapro") (part "WS2812B-MINI"))
    )
    (comp (ref "LED135")
      (value "WS2812B-Mini")
      (footprint "easyedapro:LED-SMD_4P-L3.5-W3.5-TL_WS2812B")
      (fields (field (name "Manufacturer") "worldsemi"))
      (libsource (lib "easyedapro") (part "WS2812B-MINI"))
    )
    (comp (ref "LED136")
      (value "WS2812B-Mini")
      (footprint "easyedapro:LED-SMD_4P-L3.5-W3.5-TL_WS2812B")
      (fields (field (name "Manufacturer") "worldsemi"))
      (libsource (lib "easyedapro") (part "WS2812B-MINI"))
    )
    (comp (ref "LED137")
      (value "WS2812B-Mini")
      (footprint "easyedapro:LED-SMD_4P-L3.5-W3.5-TL_WS2812B")
      (fields (field (name "Manufacturer") "worldsemi"))
      (libsource (lib "easyedapro") (part "WS2812B-MINI"))
    )
    (comp (ref "LED138")
      (value "WS2812B-Mini")
      (footprint "easyedapro:LED-SMD_4P-L3.5-W3.5-TL_WS2812B")
      (fields (field (name "Manufacturer") "worldsemi"))
      (libsource (lib "easyedapro") (part "WS2812B-MINI"))
    )
    (comp (ref "LED139")
      (value "WS2812B-Mini")
      (footprint "easyedapro:LED-SMD_4P-L3.5-W3.5-TL_WS2812B")
      (fields (field (name "Manufacturer") "worldsemi"))
      (libsource (lib "easyedapro") (part "WS2812B-MINI"))
    )
    (comp (ref "LED140")
      (value "WS2812B-Mini")
      (footprint "easyedapro:LED-SMD_4P-L3.5-W3.5-TL_WS2812B")
      (fields (field (name "Manufacturer") "worldsemi"))
      (libsource (lib "easyedapro") (part "WS2812B-MINI"))
    )
    (comp (ref "LED141")
      (value "WS2812B-Mini")
      (footprint "easyedapro:LED-SMD_4P-L3.5-W3.5-TL_WS2812B")
      (fields (field (name "Manufacturer") "worldsemi"))
      (libsource (lib "easyedapro") (part "WS2812B-MINI"))
    )
    (comp (ref "LED142")
      (value "WS2812B-Mini")
      (footprint "easyedapro:LED-SMD_4P-L3.5-W3.5-TL_WS2812B")
      (fields (field (name "Manufacturer") "worldsemi"))
      (libsource (lib "easyedapro") (part "WS2812B-MINI"))
    )
    (comp (ref "LED143")
      (value "WS2812B-Mini")
      (footprint "easyedapro:LED-SMD_4P-L3.5-W3.5-TL_WS2812B")
      (fields (field (name "Manufacturer") "worldsemi"))
      (libsource (lib "easyedapro") (part "WS2812B-MINI"))
    )
    (comp (ref "LED144")
      (value "WS2812B-Mini")
      (footprint "easyedapro:LED-SMD_4P-L3.5-W3.5-TL_WS2812B")
      (fields (field (name "Manufacturer") "worldsemi"))
      (libsource (lib "easyedapro") (part "WS2812B-MINI"))
    )
    (comp (ref "LED145")
      (value "WS2812B-Mini")
      (footprint "easyedapro:LED-SMD_4P-L3.5-W3.5-TL_WS2812B")
      (fields (field (name "Manufacturer") "worldsemi"))
      (libsource (lib "easyedapro") (part "WS2812B-MINI"))
    )
    (comp (ref "LED146")
      (value "WS2812B-Mini")
      (footprint "easyedapro:LED-SMD_4P-L3.5-W3.5-TL_WS2812B")
      (fields (field (name "Manufacturer") "worldsemi"))
      (libsource (lib "easyedapro") (part "WS2812B-MINI"))
    )
    (comp (ref "LED147")
      (value "WS2812B-Mini")
      (footprint "easyedapro:LED-SMD_4P-L3.5-W3.5-TL_WS2812B")
      (fields (field (name "Manufacturer") "worldsemi"))
      (libsource (lib "easyedapro") (part "WS2812B-MINI"))
    )
    (comp (ref "LED148")
      (value "WS2812B-Mini")
      (footprint "easyedapro:LED-SMD_4P-L3.5-W3.5-TL_WS2812B")
      (fields (field (name "Manufacturer") "worldsemi"))
      (libsource (lib "easyedapro") (part "WS2812B-MINI"))
    )
  )
  (nets
    (net (code "1") (name "+3.3V") (class "Default")
      (node (ref "C1") (pin "2") (pinfunction "2_2") (pintype "unspecified"))
      (node (ref "C14") (pin "2") (pinfunction "2_2") (pintype "unspecified"))
      (node (ref "C17") (pin "2") (pinfunction "2_2") (pintype "input"))
      (node (ref "C18") (pin "2") (pinfunction "2_2") (pintype "input"))
      (node (ref "C2") (pin "2") (pinfunction "2_2") (pintype "input"))
      (node (ref "C25") (pin "2") (pinfunction "2_2") (pintype "input"))
      (node (ref "C26") (pin "2") (pinfunction "2_2") (pintype "input"))
      (node (ref "C3") (pin "2") (pinfunction "2_2") (pintype "unspecified"))
      (node (ref "C4") (pin "2") (pinfunction "2_2") (pintype "unspecified"))
      (node (ref "C75") (pin "2") (pinfunction "2_2") (pintype "unspecified"))
      (node (ref "D21") (pin "1") (pinfunction "K_1") (pintype "unspecified"))
      (node (ref "D23") (pin "1") (pinfunction "K_1") (pintype "unspecified"))
      (node (ref "D24") (pin "1") (pinfunction "K_1") (pintype "unspecified"))
      (node (ref "R26") (pin "1") (pinfunction "1_1") (pintype "input"))
      (node (ref "R31") (pin "2") (pinfunction "2_2") (pintype "input"))
      (node (ref "R39") (pin "2") (pinfunction "2_2") (pintype "input"))
      (node (ref "U1") (pin "2") (pinfunction "3V3_2") (pintype "input"))
      (node (ref "U10") (pin "1") (pinfunction "VDD_1") (pintype "input"))
      (node (ref "U10") (pin "2") (pinfunction "MODE_2") (pintype "input"))
      (node (ref "U10") (pin "8") (pinfunction "Z_8") (pintype "input"))
      (node (ref "U11") (pin "14") (pinfunction "VCC_14") (pintype "unspecified"))
      (node (ref "U12") (pin "1") (pinfunction "VDD_1") (pintype "input"))
      (node (ref "U12") (pin "2") (pinfunction "MODE_2") (pintype "input"))
      (node (ref "U12") (pin "8") (pinfunction "Z_8") (pintype "input"))
      (node (ref "U2") (pin "2") (pinfunction "VOUT_2") (pintype "unspecified"))
      (node (ref "U30") (pin "1") (pinfunction "VDD_1") (pintype "unspecified"))
      (node (ref "U32") (pin "1") (pinfunction "VDD_1") (pintype "unspecified"))
      (node (ref "U33") (pin "1") (pinfunction "VDD_1") (pintype "unspecified"))
      (node (ref "U34") (pin "1") (pinfunction "VDD_1") (pintype "unspecified"))
      (node (ref "U35") (pin "1") (pinfunction "VDD_1") (pintype "unspecified"))
      (node (ref "U36") (pin "1") (pinfunction "VDD_1") (pintype "unspecified"))
      (node (ref "U37") (pin "1") (pinfunction "VDD_1") (pintype "unspecified"))
      (node (ref "U8") (pin "10") (pinfunction "V3_10") (pintype "unspecified"))
      (node (ref "U8") (pin "7") (pinfunction "VCC_7") (pintype "unspecified"))
      (node (ref "ZD1") (pin "1") (pinfunction "K_1") (pintype "unspecified"))
    )
    (net (code "2") (name "5V") (class "Default")
      (node (ref "C13") (pin "2") (pinfunction "2_2") (pintype "unspecified"))
      (node (ref "C64") (pin "1") (pinfunction "1_1") (pintype "unspecified"))
      (node (ref "C65") (pin "1") (pinfunction "1_1") (pintype "unspecified"))
      (node (ref "C66") (pin "1") (pinfunction "1_1") (pintype "unspecified"))
      (node (ref "C67") (pin "2") (pinfunction "2_2") (pintype "unspecified"))
      (node (ref "C68") (pin "1") (pinfunction "1_1") (pintype "unspecified"))
      (node (ref "C69") (pin "1") (pinfunction "1_1") (pintype "unspecified"))
      (node (ref "C70") (pin "1") (pinfunction "1_1") (pintype "unspecified"))
      (node (ref "C71") (pin "2") (pinfunction "2_2") (pintype "unspecified"))
      (node (ref "C72") (pin "2") (pinfunction "2_2") (pintype "unspecified"))
      (node (ref "C73") (pin "2") (pinfunction "2_2") (pintype "unspecified"))
      (node (ref "C74") (pin "2") (pinfunction "2_2") (pintype "unspecified"))
      (node (ref "C76") (pin "2") (pinfunction "2_2") (pintype "unspecified"))
      (node (ref "C77") (pin "2") (pinfunction "2_2") (pintype "unspecified"))
      (node (ref "C78") (pin "2") (pinfunction "2_2") (pintype "unspecified"))
      (node (ref "C79") (pin "2") (pinfunction "2_2") (pintype "unspecified"))
      (node (ref "D20") (pin "1") (pinfunction "K_1") (pintype "unspecified"))
      (node (ref "L1") (pin "1") (pinfunction "1_1") (pintype "unspecified"))
      (node (ref "LED105") (pin "1") (pinfunction "VDD_1") (pintype "input"))
      (node (ref "LED106") (pin "1") (pinfunction "VDD_1") (pintype "input"))
      (node (ref "LED107") (pin "1") (pinfunction "VDD_1") (pintype "input"))
      (node (ref "LED108") (pin "1") (pinfunction "VDD_1") (pintype "input"))
      (node (ref "LED109") (pin "1") (pinfunction "VDD_1") (pintype "input"))
      (node (ref "LED110") (pin "1") (pinfunction "VDD_1") (pintype "input"))
      (node (ref "LED111") (pin "1") (pinfunction "VDD_1") (pintype "input"))
      (node (ref "LED112") (pin "1") (pinfunction "VDD_1") (pintype "input"))
      (node (ref "LED113") (pin "1") (pinfunction "VDD_1") (pintype "input"))
      (node (ref "LED114") (pin "1") (pinfunction "VDD_1") (pintype "input"))
      (node (ref "LED115") (pin "1") (pinfunction "VDD_1") (pintype "input"))
      (node (ref "LED116") (pin "1") (pinfunction "VDD_1") (pintype "input"))
      (node (ref "LED117") (pin "1") (pinfunction "VDD_1") (pintype "input"))
      (node (ref "LED118") (pin "1") (pinfunction "VDD_1") (pintype "input"))
      (node (ref "LED119") (pin "1") (pinfunction "VDD_1") (pintype "input"))
      (node (ref "LED120") (pin "1") (pinfunction "VDD_1") (pintype "input"))
      (node (ref "LED121") (pin "1") (pinfunction "VDD_1") (pintype "input"))
      (node (ref "LED122") (pin "1") (pinfunction "VDD_1") (pintype "input"))
      (node (ref "LED123") (pin "1") (pinfunction "VDD_1") (pintype "input"))
      (node (ref "LED124") (pin "1") (pinfunction "VDD_1") (pintype "input"))
      (node (ref "LED125") (pin "1") (pinfunction "VDD_1") (pintype "input"))
      (node (ref "LED126") (pin "1") (pinfunction "VDD_1") (pintype "input"))
      (node (ref "LED127") (pin "1") (pinfunction "VDD_1") (pintype "input"))
      (node (ref "LED128") (pin "1") (pinfunction "VDD_1") (pintype "input"))
      (node (ref "LED129") (pin "1") (pinfunction "VDD_1") (pintype "input"))
      (node (ref "LED130") (pin "1") (pinfunction "VDD_1") (pintype "input"))
      (node (ref "LED131") (pin "1") (pinfunction "VDD_1") (pintype "input"))
      (node (ref "LED132") (pin "1") (pinfunction "VDD_1") (pintype "input"))
      (node (ref "LED133") (pin "1") (pinfunction "VDD_1") (pintype "input"))
      (node (ref "LED134") (pin "1") (pinfunction "VDD_1") (pintype "input"))
      (node (ref "LED135") (pin "1") (pinfunction "VDD_1") (pintype "input"))
      (node (ref "LED136") (pin "1") (pinfunction "VDD_1") (pintype "input"))
      (node (ref "LED137") (pin "1") (pinfunction "VDD_1") (pintype "input"))
      (node (ref "LED138") (pin "1") (pinfunction "VDD_1") (pintype "input"))
      (node (ref "LED139") (pin "1") (pinfunction "VDD_1") (pintype "input"))
      (node (ref "LED140") (pin "1") (pinfunction "VDD_1") (pintype "input"))
      (node (ref "LED141") (pin "1") (pinfunction "VDD_1") (pintype "input"))
      (node (ref "LED142") (pin "1") (pinfunction "VDD_1") (pintype "input"))
      (node (ref "LED143") (pin "1") (pinfunction "VDD_1") (pintype "input"))
      (node (ref "LED144") (pin "1") (pinfunction "VDD_1") (pintype "input"))
      (node (ref "LED145") (pin "1") (pinfunction "VDD_1") (pintype "input"))
      (node (ref "LED146") (pin "1") (pinfunction "VDD_1") (pintype "input"))
      (node (ref "LED147") (pin "1") (pinfunction "VDD_1") (pintype "input"))
      (node (ref "LED148") (pin "1") (pinfunction "VDD_1") (pintype "input"))
      (node (ref "LED62") (pin "3") (pinfunction "VDD_3") (pintype "unspecified"))
      (node (ref "LED63") (pin "3") (pinfunction "VDD_3") (pintype "unspecified"))
      (node (ref "LED64") (pin "3") (pinfunction "VDD_3") (pintype "unspecified"))
      (node (ref "LED65") (pin "3") (pinfunction "VDD_3") (pintype "unspecified"))
      (node (ref "LED66") (pin "3") (pinfunction "VDD_3") (pintype "unspecified"))
      (node (ref "LED67") (pin "3") (pinfunction "VDD_3") (pintype "unspecified"))
      (node (ref "LED68") (pin "3") (pinfunction "VDD_3") (pintype "unspecified"))
      (node (ref "U2") (pin "3") (pinfunction "VIN_3") (pintype "unspecified"))
      (node (ref "U31") (pin "16") (pinfunction "VCC_16") (pintype "input"))
      (node (ref "U38") (pin "4") (pinfunction "EN_4") (pintype "input"))
      (node (ref "U38") (pin "5") (pinfunction "IN_5") (pintype "input"))
      (node (ref "USB1") (pin "A4") (pinfunction "VBUS_A4") (pintype "input"))
      (node (ref "USB1") (pin "A9") (pinfunction "VBUS_A9") (pintype "input"))
      (node (ref "USB1") (pin "B4") (pinfunction "VBUS_B4") (pintype "input"))
      (node (ref "USB1") (pin "B9") (pinfunction "VBUS_B9") (pintype "input"))
    )
    (net (code "3") (name "12V") (class "Default")
      (node (ref "C19") (pin "1") (pinfunction "1_1") (pintype "input"))
      (node (ref "C20") (pin "2") (pinfunction "2_2") (pintype "input"))
      (node (ref "C27") (pin "1") (pinfunction "1_1") (pintype "input"))
      (node (ref "C28") (pin "1") (pinfunction "1_1") (pintype "input"))
      (node (ref "C29") (pin "2") (pinfunction "2_2") (pintype "input"))
      (node (ref "C5") (pin "1") (pinfunction "1_1") (pintype "input"))
      (node (ref "C8") (pin "2") (pinfunction "2_2") (pintype "unspecified"))
      (node (ref "C9") (pin "2") (pinfunction "2_2") (pintype "unspecified"))
      (node (ref "D1") (pin "1") (pinfunction "K_1") (pintype "unspecified"))
      (node (ref "D11") (pin "2") (pinfunction "A_2") (pintype "input"))
      (node (ref "D12") (pin "2") (pinfunction "A_2") (pintype "input"))
      (node (ref "D13") (pin "2") (pinfunction "A_2") (pintype "input"))
      (node (ref "D2") (pin "2") (pinfunction "A_2") (pintype "input"))
      (node (ref "D27") (pin "2") (pinfunction "2_2") (pintype "unspecified"))
      (node (ref "D28") (pin "2") (pinfunction "2_2") (pintype "unspecified"))
      (node (ref "D29") (pin "2") (pinfunction "2_2") (pintype "unspecified"))
      (node (ref "D3") (pin "2") (pinfunction "A_2") (pintype "input"))
      (node (ref "D4") (pin "2") (pinfunction "A_2") (pintype "input"))
      (node (ref "Q12") (pin "3") (pinfunction "D_3") (pintype "input"))
      (node (ref "Q14") (pin "3") (pinfunction "D_3") (pintype "input"))
      (node (ref "Q16") (pin "3") (pinfunction "D_3") (pintype "input"))
      (node (ref "Q18") (pin "3") (pinfunction "D_3") (pintype "input"))
      (node (ref "Q20") (pin "3") (pinfunction "D_3") (pintype "input"))
      (node (ref "Q22") (pin "3") (pinfunction "D_3") (pintype "input"))
      (node (ref "R16") (pin "2") (pinfunction "2_2") (pintype "unspecified"))
      (node (ref "R38") (pin "2") (pinfunction "2_2") (pintype "unspecified"))
      (node (ref "U13") (pin "7") (pinfunction "VCC_7") (pintype "input"))
      (node (ref "U9") (pin "7") (pinfunction "VCC_7") (pintype "input"))
    )
    (net (code "4") (name "ADC1") (class "Default")
      (node (ref "U1") (pin "12") (pinfunction "IO8_12") (pintype "input"))
      (node (ref "U31") (pin "13") (pinfunction "X_13") (pintype "input"))
    )
    (net (code "5") (name "ADC2") (class "Default")
      (node (ref "U1") (pin "21") (pinfunction "IO13_21") (pintype "input"))
      (node (ref "U31") (pin "3") (pinfunction "Y_3") (pintype "input"))
    )
    (net (code "6") (name "BT_1") (class "Default")
      (node (ref "C51") (pin "2") (pinfunction "2_2") (pintype "unspecified"))
      (node (ref "U31") (pin "1") (pinfunction "Y0_1") (pintype "input"))
      (node (ref "U32") (pin "3") (pinfunction "VOUT_3") (pintype "unspecified"))
    )
    (net (code "7") (name "BT_2") (class "Default")
      (node (ref "C52") (pin "2") (pinfunction "2_2") (pintype "unspecified"))
      (node (ref "U31") (pin "5") (pinfunction "Y1_5") (pintype "input"))
      (node (ref "U33") (pin "3") (pinfunction "VOUT_3") (pintype "unspecified"))
    )
    (net (code "8") (name "BT_3") (class "Default")
      (node (ref "C53") (pin "2") (pinfunction "2_2") (pintype "unspecified"))
      (node (ref "U31") (pin "2") (pinfunction "Y2_2") (pintype "input"))
      (node (ref "U34") (pin "3") (pinfunction "VOUT_3") (pintype "unspecified"))
    )
    (net (code "9") (name "BT_4") (class "Default")
      (node (ref "C54") (pin "2") (pinfunction "2_2") (pintype "unspecified"))
      (node (ref "U31") (pin "4") (pinfunction "Y3_4") (pintype "input"))
      (node (ref "U35") (pin "3") (pinfunction "VOUT_3") (pintype "unspecified"))
    )
    (net (code "10") (name "D+") (class "Default")
      (node (ref "U8") (pin "1") (pinfunction "UD+_1") (pintype "unspecified"))
      (node (ref "USB1") (pin "A6") (pinfunction "DP1_A6") (pintype "input"))
      (node (ref "USB1") (pin "B6") (pinfunction "DP2_B6") (pintype "input"))
    )
    (net (code "11") (name "D-") (class "Default")
      (node (ref "U8") (pin "2") (pinfunction "UD-_2") (pintype "unspecified"))
      (node (ref "USB1") (pin "A7") (pinfunction "DN1_A7") (pintype "input"))
      (node (ref "USB1") (pin "B7") (pinfunction "DN2_B7") (pintype "input"))
    )
    (net (code "12") (name "EN") (class "Default")
      (node (ref "R26") (pin "2") (pinfunction "2_2") (pintype "input"))
      (node (ref "U1") (pin "3") (pinfunction "EN_3") (pintype "input"))
      (node (ref "U8") (pin "4") (pinfunction "RTS#_4") (pintype "unspecified"))
    )
    (net (code "13") (name "FX_L") (class "Default")
      (node (ref "C55") (pin "2") (pinfunction "2_2") (pintype "unspecified"))
      (node (ref "U31") (pin "12") (pinfunction "X0_12") (pintype "input"))
      (node (ref "U36") (pin "3") (pinfunction "VOUT_3") (pintype "unspecified"))
    )
    (net (code "14") (name "FX_R") (class "Default")
      (node (ref "C56") (pin "2") (pinfunction "2_2") (pintype "unspecified"))
      (node (ref "U31") (pin "14") (pinfunction "X1_14") (pintype "input"))
      (node (ref "U37") (pin "3") (pinfunction "VOUT_3") (pintype "unspecified"))
    )
    (net (code "15") (name "GND") (class "Default")
      (node (ref "C1") (pin "1") (pinfunction "1_1") (pintype "unspecified"))
      (node (ref "C13") (pin "1") (pinfunction "1_1") (pintype "unspecified"))
      (node (ref "C14") (pin "1") (pinfunction "1_1") (pintype "unspecified"))
      (node (ref "C17") (pin "1") (pinfunction "1_1") (pintype "input"))
      (node (ref "C18") (pin "1") (pinfunction "1_1") (pintype "input"))
      (node (ref "C19") (pin "2") (pinfunction "2_2") (pintype "input"))
      (node (ref "C2") (pin "1") (pinfunction "1_1") (pintype "input"))
      (node (ref "C20") (pin "1") (pinfunction "1_1") (pintype "input"))
      (node (ref "C24") (pin "2") (pinfunction "2_2") (pintype "input"))
      (node (ref "C25") (pin "1") (pinfunction "1_1") (pintype "input"))
      (node (ref "C26") (pin "1") (pinfunction "1_1") (pintype "input"))
      (node (ref "C27") (pin "2") (pinfunction "2_2") (pintype "input"))
      (node (ref "C28") (pin "2") (pinfunction "2_2") (pintype "input"))
      (node (ref "C29") (pin "1") (pinfunction "1_1") (pintype "input"))
      (node (ref "C3") (pin "1") (pinfunction "1_1") (pintype "unspecified"))
      (node (ref "C4") (pin "1") (pinfunction "1_1") (pintype "unspecified"))
      (node (ref "C5") (pin "2") (pinfunction "2_2") (pintype "input"))
      (node (ref "C50") (pin "1") (pinfunction "1_1") (pintype "unspecified"))
      (node (ref "C51") (pin "1") (pinfunction "1_1") (pintype "unspecified"))
      (node (ref "C52") (pin "1") (pinfunction "1_1") (pintype "unspecified"))
      (node (ref "C53") (pin "1") (pinfunction "1_1") (pintype "unspecified"))
      (node (ref "C54") (pin "1") (pinfunction "1_1") (pintype "unspecified"))
      (node (ref "C55") (pin "1") (pinfunction "1_1") (pintype "unspecified"))
      (node (ref "C56") (pin "1") (pinfunction "1_1") (pintype "unspecified"))
      (node (ref "C64") (pin "2") (pinfunction "2_2") (pintype "unspecified"))
      (node (ref "C65") (pin "2") (pinfunction "2_2") (pintype "unspecified"))
      (node (ref "C66") (pin "2") (pinfunction "2_2") (pintype "unspecified"))
      (node (ref "C67") (pin "1") (pinfunction "1_1") (pintype "unspecified"))
      (node (ref "C68") (pin "2") (pinfunction "2_2") (pintype "unspecified"))
      (node (ref "C69") (pin "2") (pinfunction "2_2") (pintype "unspecified"))
      (node (ref "C70") (pin "2") (pinfunction "2_2") (pintype "unspecified"))
      (node (ref "C71") (pin "1") (pinfunction "1_1") (pintype "unspecified"))
      (node (ref "C72") (pin "1") (pinfunction "1_1") (pintype "unspecified"))
      (node (ref "C73") (pin "1") (pinfunction "1_1") (pintype "unspecified"))
      (node (ref "C74") (pin "1") (pinfunction "1_1") (pintype "unspecified"))
      (node (ref "C75") (pin "1") (pinfunction "1_1") (pintype "unspecified"))
      (node (ref "C76") (pin "1") (pinfunction "1_1") (pintype "unspecified"))
      (node (ref "C77") (pin "1") (pinfunction "1_1") (pintype "unspecified"))
      (node (ref "C78") (pin "1") (pinfunction "1_1") (pintype "unspecified"))
      (node (ref "C79") (pin "1") (pinfunction "1_1") (pintype "unspecified"))
      (node (ref "C8") (pin "1") (pinfunction "1_1") (pintype "unspecified"))
      (node (ref "C80") (pin "1") (pinfunction "1_1") (pintype "unspecified"))
      (node (ref "C81") (pin "1") (pinfunction "1_1") (pintype "unspecified"))
      (node (ref "C82") (pin "1") (pinfunction "1_1") (pintype "unspecified"))
      (node (ref "C83") (pin "1") (pinfunction "1_1") (pintype "unspecified"))
      (node (ref "C84") (pin "1") (pinfunction "1_1") (pintype "unspecified"))
      (node (ref "C85") (pin "1") (pinfunction "1_1") (pintype "unspecified"))
      (node (ref "C86") (pin "1") (pinfunction "1_1") (pintype "unspecified"))
      (node (ref "C87") (pin "1") (pinfunction "1_1") (pintype "unspecified"))
      (node (ref "C88") (pin "1") (pinfunction "1_1") (pintype "unspecified"))
      (node (ref "C89") (pin "1") (pinfunction "1_1") (pintype "unspecified"))
      (node (ref "C9") (pin "1") (pinfunction "1_1") (pintype "unspecified"))
      (node (ref "CN3") (pin "4") (pinfunction "4_4") (pintype "input"))
      (node (ref "CN3") (pin "5") (pinfunction "5_5") (pintype "input"))
      (node (ref "CN4") (pin "4") (pinfunction "4_4") (pintype "input"))
      (node (ref "CN4") (pin "5") (pinfunction "5_5") (pintype "input"))
      (node (ref "D20") (pin "2") (pinfunction "A_2") (pintype "unspecified"))
      (node (ref "D21") (pin "2") (pinfunction "A_2") (pintype "unspecified"))
      (node (ref "D23") (pin "2") (pinfunction "A_2") (pintype "unspecified"))
      (node (ref "D24") (pin "2") (pinfunction "A_2") (pintype "unspecified"))
      (node (ref "D27") (pin "1") (pinfunction "1_1") (pintype "unspecified"))
      (node (ref "D28") (pin "1") (pinfunction "1_1") (pintype "unspecified"))
      (node (ref "D29") (pin "1") (pinfunction "1_1") (pintype "unspecified"))
      (node (ref "LED105") (pin "3") (pinfunction "VSS_3") (pintype "input"))
      (node (ref "LED106") (pin "3") (pinfunction "VSS_3") (pintype "input"))
      (node (ref "LED107") (pin "3") (pinfunction "VSS_3") (pintype "input"))
      (node (ref "LED108") (pin "3") (pinfunction "VSS_3") (pintype "input"))
      (node (ref "LED109") (pin "3") (pinfunction "VSS_3") (pintype "input"))
      (node (ref "LED110") (pin "3") (pinfunction "VSS_3") (pintype "input"))
      (node (ref "LED111") (pin "3") (pinfunction "VSS_3") (pintype "input"))
      (node (ref "LED112") (pin "3") (pinfunction "VSS_3") (pintype "input"))
      (node (ref "LED113") (pin "3") (pinfunction "VSS_3") (pintype "input"))
      (node (ref "LED114") (pin "3") (pinfunction "VSS_3") (pintype "input"))
      (node (ref "LED115") (pin "3") (pinfunction "VSS_3") (pintype "input"))
      (node (ref "LED116") (pin "3") (pinfunction "VSS_3") (pintype "input"))
      (node (ref "LED117") (pin "3") (pinfunction "VSS_3") (pintype "input"))
      (node (ref "LED118") (pin "3") (pinfunction "VSS_3") (pintype "input"))
      (node (ref "LED119") (pin "3") (pinfunction "VSS_3") (pintype "input"))
      (node (ref "LED120") (pin "3") (pinfunction "VSS_3") (pintype "input"))
      (node (ref "LED121") (pin "3") (pinfunction "VSS_3") (pintype "input"))
      (node (ref "LED122") (pin "3") (pinfunction "VSS_3") (pintype "input"))
      (node (ref "LED123") (pin "3") (pinfunction "VSS_3") (pintype "input"))
      (node (ref "LED124") (pin "3") (pinfunction "VSS_3") (pintype "input"))
      (node (ref "LED125") (pin "3") (pinfunction "VSS_3") (pintype "input"))
      (node (ref "LED126") (pin "3") (pinfunction "VSS_3") (pintype "input"))
      (node (ref "LED127") (pin "3") (pinfunction "VSS_3") (pintype "input"))
      (node (ref "LED128") (pin "3") (pinfunction "VSS_3") (pintype "input"))
      (node (ref "LED129") (pin "3") (pinfunction "VSS_3") (pintype "input"))
      (node (ref "LED130") (pin "3") (pinfunction "VSS_3") (pintype "input"))
      (node (ref "LED131") (pin "3") (pinfunction "VSS_3") (pintype "input"))
      (node (ref "LED132") (pin "3") (pinfunction "VSS_3") (pintype "input"))
      (node (ref "LED133") (pin "3") (pinfunction "VSS_3") (pintype "input"))
      (node (ref "LED134") (pin "3") (pinfunction "VSS_3") (pintype "input"))
      (node (ref "LED135") (pin "3") (pinfunction "VSS_3") (pintype "input"))
      (node (ref "LED136") (pin "3") (pinfunction "VSS_3") (pintype "input"))
      (node (ref "LED137") (pin "3") (pinfunction "VSS_3") (pintype "input"))
      (node (ref "LED138") (pin "3") (pinfunction "VSS_3") (pintype "input"))
      (node (ref "LED139") (pin "3") (pinfunction "VSS_3") (pintype "input"))
      (node (ref "LED140") (pin "3") (pinfunction "VSS_3") (pintype "input"))
      (node (ref "LED141") (pin "3") (pinfunction "VSS_3") (pintype "input"))
      (node (ref "LED142") (pin "3") (pinfunction "VSS_3") (pintype "input"))
      (node (ref "LED143") (pin "3") (pinfunction "VSS_3") (pintype "input"))
      (node (ref "LED144") (pin "3") (pinfunction "VSS_3") (pintype "input"))
      (node (ref "LED145") (pin "3") (pinfunction "VSS_3") (pintype "input"))
      (node (ref "LED146") (pin "3") (pinfunction "VSS_3") (pintype "input"))
      (node (ref "LED147") (pin "3") (pinfunction "VSS_3") (pintype "input"))
      (node (ref "LED148") (pin "3") (pinfunction "VSS_3") (pintype "input"))
      (node (ref "LED2") (pin "1") (pinfunction "K_1") (pintype "unspecified"))
      (node (ref "LED3") (pin "1") (pinfunction "K_1") (pintype "unspecified"))
      (node (ref "LED62") (pin "1") (pinfunction "GND_1") (pintype "unspecified"))
      (node (ref "LED63") (pin "1") (pinfunction "GND_1") (pintype "unspecified"))
      (node (ref "LED64") (pin "1") (pinfunction "GND_1") (pintype "unspecified"))
      (node (ref "LED65") (pin "1") (pinfunction "GND_1") (pintype "unspecified"))
      (node (ref "LED66") (pin "1") (pinfunction "GND_1") (pintype "unspecified"))
      (node (ref "LED67") (pin "1") (pinfunction "GND_1") (pintype "unspecified"))
      (node (ref "LED68") (pin "1") (pinfunction "GND_1") (pintype "unspecified"))
      (node (ref "Q13") (pin "2") (pinfunction "S_2") (pintype "input"))
      (node (ref "Q15") (pin "2") (pinfunction "S_2") (pintype "input"))
      (node (ref "Q17") (pin "2") (pinfunction "S_2") (pintype "input"))
      (node (ref "Q19") (pin "2") (pinfunction "S_2") (pintype "input"))
      (node (ref "Q21") (pin "2") (pinfunction "S_2") (pintype "input"))
      (node (ref "Q23") (pin "2") (pinfunction "S_2") (pintype "input"))
      (node (ref "R3") (pin "1") (pinfunction "1_1") (pintype "unspecified"))
      (node (ref "R51") (pin "1") (pinfunction "1_1") (pintype "unspecified"))
      (node (ref "R52") (pin "1") (pinfunction "1_1") (pintype "unspecified"))
      (node (ref "R53") (pin "1") (pinfunction "1_1") (pintype "unspecified"))
      (node (ref "R54") (pin "1") (pinfunction "1_1") (pintype "unspecified"))
      (node (ref "R55") (pin "1") (pinfunction "1_1") (pintype "unspecified"))
      (node (ref "R56") (pin "1") (pinfunction "1_1") (pintype "unspecified"))
      (node (ref "R57") (pin "1") (pinfunction "1_1") (pintype "unspecified"))
      (node (ref "R58") (pin "1") (pinfunction "1_1") (pintype "unspecified"))
      (node (ref "R59") (pin "1") (pinfunction "1_1") (pintype "unspecified"))
      (node (ref "R60") (pin "1") (pinfunction "1_1") (pintype "unspecified"))
      (node (ref "R61") (pin "1") (pinfunction "1_1") (pintype "input"))
      (node (ref "R62") (pin "2") (pinfunction "2_2") (pintype "input"))
      (node (ref "U1") (pin "1") (pinfunction "GND_1") (pintype "input"))
      (node (ref "U1") (pin "40") (pinfunction "GND_40") (pintype "input"))
      (node (ref "U1") (pin "41") (pinfunction "GND_41") (pintype "input"))
      (node (ref "U10") (pin "4") (pinfunction "GND_4") (pintype "input"))
      (node (ref "U11") (pin "1") (pinfunction "A0_1") (pintype "unspecified"))
      (node (ref "U11") (pin "2") (pinfunction "A1_2") (pintype "unspecified"))
      (node (ref "U11") (pin "7") (pinfunction "GND_7") (pintype "unspecified"))
      (node (ref "U12") (pin "4") (pinfunction "GND_4") (pintype "input"))
      (node (ref "U13") (pin "8") (pinfunction "GND_8") (pintype "input"))
      (node (ref "U2") (pin "1") (pinfunction "VSS_1") (pintype "unspecified"))
      (node (ref "U30") (pin "2") (pinfunction "GND_2") (pintype "unspecified"))
      (node (ref "U31") (pin "6") (pinfunction "#ENABLE_6") (pintype "input"))
      (node (ref "U31") (pin "8") (pinfunction "GND_8") (pintype "input"))
      (node (ref "U32") (pin "2") (pinfunction "GND_2") (pintype "unspecified"))
      (node (ref "U33") (pin "2") (pinfunction "GND_2") (pintype "unspecified"))
      (node (ref "U34") (pin "2") (pinfunction "GND_2") (pintype "unspecified"))
      (node (ref "U35") (pin "2") (pinfunction "GND_2") (pintype "unspecified"))
      (node (ref "U36") (pin "2") (pinfunction "GND_2") (pintype "unspecified"))
      (node (ref "U37") (pin "2") (pinfunction "GND_2") (pintype "unspecified"))
      (node (ref "U38") (pin "2") (pinfunction "GND_2") (pintype "input"))
      (node (ref "U8") (pin "3") (pinfunction "GND_3") (pintype "unspecified"))
      (node (ref "U9") (pin "8") (pinfunction "GND_8") (pintype "input"))
      (node (ref "USB1") (pin "A1") (pinfunction "GND_A1") (pintype "input"))
      (node (ref "USB1") (pin "A12") (pinfunction "GND_A12") (pintype "input"))
      (node (ref "USB1") (pin "B1") (pinfunction "GND_B1") (pintype "input"))
      (node (ref "USB1") (pin "B12") (pinfunction "GND_B12") (pintype "input"))
      (node (ref "ZD1") (pin "2") (pinfunction "A_2") (pintype "unspecified"))
    )
    (net (code "16") (name "HO1_0") (class "Default")
      (node (ref "D10") (pin "1") (pinfunction "K_1") (pintype "input"))
      (node (ref "R27") (pin "1") (pinfunction "1_1") (pintype "input"))
      (node (ref "U9") (pin "19") (pinfunction "HO1_19") (pintype "input"))
    )
    (net (code "17") (name "HO1_1") (class "Default")
      (node (ref "D14") (pin "1") (pinfunction "K_1") (pintype "input"))
      (node (ref "R32") (pin "1") (pinfunction "1_1") (pintype "input"))
      (node (ref "U13") (pin "19") (pinfunction "HO1_19") (pintype "input"))
    )
    (net (code "18") (name "HO2_0") (class "Default")
      (node (ref "D6") (pin "1") (pinfunction "K_1") (pintype "input"))
      (node (ref "R5") (pin "1") (pinfunction "1_1") (pintype "input"))
      (node (ref "U9") (pin "16") (pinfunction "HO2_16") (pintype "input"))
    )
    (net (code "19") (name "HO2_1") (class "Default")
      (node (ref "D16") (pin "1") (pinfunction "K_1") (pintype "input"))
      (node (ref "R34") (pin "1") (pinfunction "1_1") (pintype "input"))
      (node (ref "U13") (pin "16") (pinfunction "HO2_16") (pintype "input"))
    )
    (net (code "20") (name "HO3_0") (class "Default")
      (node (ref "D8") (pin "1") (pinfunction "K_1") (pintype "input"))
      (node (ref "R29") (pin "1") (pinfunction "1_1") (pintype "input"))
      (node (ref "U9") (pin "13") (pinfunction "HO3_13") (pintype "input"))
    )
    (net (code "21") (name "HO3_1") (class "Default")
      (node (ref "D18") (pin "1") (pinfunction "K_1") (pintype "input"))
      (node (ref "R36") (pin "1") (pinfunction "1_1") (pintype "input"))
      (node (ref "U13") (pin "13") (pinfunction "HO3_13") (pintype "input"))
    )
    (net (code "22") (name "IO0") (class "Default")
      (node (ref "R25") (pin "2") (pinfunction "2_2") (pintype "input"))
      (node (ref "U1") (pin "27") (pinfunction "IO0_27") (pintype "input"))
      (node (ref "U8") (pin "6") (pinfunction "TNOW/DTR#_6") (pintype "unspecified"))
    )
    (net (code "23") (name "IO_ON_OFF") (class "Default")
      (node (ref "U1") (pin "11") (pinfunction "IO18_11") (pintype "input"))
    )
    (net (code "24") (name "LED") (class "Default")
      (node (ref "LED148") (pin "2") (pinfunction "DOUT_2") (pintype "input"))
      (node (ref "LED62") (pin "2") (pinfunction "DI_2") (pintype "unspecified"))
    )
    (net (code "25") (name "LO1_0") (class "Default")
      (node (ref "D5") (pin "1") (pinfunction "K_1") (pintype "input"))
      (node (ref "R28") (pin "1") (pinfunction "1_1") (pintype "input"))
      (node (ref "U9") (pin "11") (pinfunction "LO1_11") (pintype "input"))
    )
    (net (code "26") (name "LO1_1") (class "Default")
      (node (ref "D15") (pin "1") (pinfunction "K_1") (pintype "input"))
      (node (ref "R33") (pin "1") (pinfunction "1_1") (pintype "input"))
      (node (ref "U13") (pin "11") (pinfunction "LO1_11") (pintype "input"))
    )
    (net (code "27") (name "LO2_0") (class "Default")
      (node (ref "D7") (pin "1") (pinfunction "K_1") (pintype "input"))
      (node (ref "R6") (pin "1") (pinfunction "1_1") (pintype "input"))
      (node (ref "U9") (pin "10") (pinfunction "LO2_10") (pintype "input"))
    )
    (net (code "28") (name "LO2_1") (class "Default")
      (node (ref "D17") (pin "1") (pinfunction "K_1") (pintype "input"))
      (node (ref "R35") (pin "1") (pinfunction "1_1") (pintype "input"))
      (node (ref "U13") (pin "10") (pinfunction "LO2_10") (pintype "input"))
    )
    (net (code "29") (name "LO3_0") (class "Default")
      (node (ref "D9") (pin "1") (pinfunction "K_1") (pintype "input"))
      (node (ref "R30") (pin "1") (pinfunction "1_1") (pintype "input"))
      (node (ref "U9") (pin "9") (pinfunction "LO3_9") (pintype "input"))
    )
    (net (code "30") (name "LO3_1") (class "Default")
      (node (ref "D19") (pin "1") (pinfunction "K_1") (pintype "input"))
      (node (ref "R37") (pin "1") (pinfunction "1_1") (pintype "input"))
      (node (ref "U13") (pin "9") (pinfunction "LO3_9") (pintype "input"))
    )
    (net (code "31") (name "M0_IN1_0") (class "Default")
      (node (ref "U1") (pin "10") (pinfunction "IO17_10") (pintype "input"))
      (node (ref "U9") (pin "1") (pinfunction "HIN1_1") (pintype "input"))
      (node (ref "U9") (pin "4") (pinfunction "LIN1#_4") (pintype "input"))
    )
    (net (code "32") (name "M0_IN1_1") (class "Default")
      (node (ref "U1") (pin "18") (pinfunction "IO10_18") (pintype "input"))
      (node (ref "U13") (pin "1") (pinfunction "HIN1_1") (pintype "input"))
      (node (ref "U13") (pin "4") (pinfunction "LIN1#_4") (pintype "input"))
    )
    (net (code "33") (name "M0_IN2_0") (class "Default")
      (node (ref "U1") (pin "9") (pinfunction "IO16_9") (pintype "input"))
      (node (ref "U9") (pin "2") (pinfunction "HIN2_2") (pintype "input"))
      (node (ref "U9") (pin "5") (pinfunction "LIN2#_5") (pintype "input"))
    )
    (net (code "34") (name "M0_IN2_1") (class "Default")
      (node (ref "U1") (pin "19") (pinfunction "IO11_19") (pintype "input"))
      (node (ref "U13") (pin "2") (pinfunction "HIN2_2") (pintype "input"))
      (node (ref "U13") (pin "5") (pinfunction "LIN2#_5") (pintype "input"))
    )
    (net (code "35") (name "M0_IN3_0") (class "Default")
      (node (ref "U1") (pin "8") (pinfunction "IO15_8") (pintype "input"))
      (node (ref "U9") (pin "3") (pinfunction "HIN3_3") (pintype "input"))
      (node (ref "U9") (pin "6") (pinfunction "LIN3#_6") (pintype "input"))
    )
    (net (code "36") (name "M0_IN3_1") (class "Default")
      (node (ref "U1") (pin "20") (pinfunction "IO12_20") (pintype "input"))
      (node (ref "U13") (pin "3") (pinfunction "HIN3_3") (pintype "input"))
      (node (ref "U13") (pin "6") (pinfunction "LIN3#_6") (pintype "input"))
    )
    (net (code "37") (name "Net-(C80-Pad2)") (class "Default")
      (node (ref "C80") (pin "2") (pinfunction "2_2") (pintype "unspecified"))
      (node (ref "R51") (pin "2") (pinfunction "2_2") (pintype "unspecified"))
    )
    (net (code "38") (name "Net-(C81-Pad2)") (class "Default")
      (node (ref "C81") (pin "2") (pinfunction "2_2") (pintype "unspecified"))
      (node (ref "R52") (pin "2") (pinfunction "2_2") (pintype "unspecified"))
    )
    (net (code "39") (name "Net-(C82-Pad2)") (class "Default")
      (node (ref "C82") (pin "2") (pinfunction "2_2") (pintype "unspecified"))
      (node (ref "R53") (pin "2") (pinfunction "2_2") (pintype "unspecified"))
    )
    (net (code "40") (name "Net-(C83-Pad2)") (class "Default")
      (node (ref "C83") (pin "2") (pinfunction "2_2") (pintype "unspecified"))
      (node (ref "R54") (pin "2") (pinfunction "2_2") (pintype "unspecified"))
    )
    (net (code "41") (name "Net-(C84-Pad2)") (class "Default")
      (node (ref "C84") (pin "2") (pinfunction "2_2") (pintype "unspecified"))
      (node (ref "R59") (pin "2") (pinfunction "2_2") (pintype "unspecified"))
    )
    (net (code "42") (name "Net-(C85-Pad2)") (class "Default")
      (node (ref "C85") (pin "2") (pinfunction "2_2") (pintype "unspecified"))
      (node (ref "R58") (pin "2") (pinfunction "2_2") (pintype "unspecified"))
    )
    (net (code "43") (name "Net-(C86-Pad2)") (class "Default")
      (node (ref "C86") (pin "2") (pinfunction "2_2") (pintype "unspecified"))
      (node (ref "R57") (pin "2") (pinfunction "2_2") (pintype "unspecified"))
    )
    (net (code "44") (name "Net-(C87-Pad2)") (class "Default")
      (node (ref "C87") (pin "2") (pinfunction "2_2") (pintype "unspecified"))
      (node (ref "R56") (pin "2") (pinfunction "2_2") (pintype "unspecified"))
    )
    (net (code "45") (name "Net-(C88-Pad2)") (class "Default")
      (node (ref "C88") (pin "2") (pinfunction "2_2") (pintype "unspecified"))
      (node (ref "R55") (pin "2") (pinfunction "2_2") (pintype "unspecified"))
    )
    (net (code "46") (name "Net-(C89-Pad2)") (class "Default")
      (node (ref "C89") (pin "2") (pinfunction "2_2") (pintype "unspecified"))
      (node (ref "R60") (pin "2") (pinfunction "2_2") (pintype "unspecified"))
      (node (ref "USB1") (pin "1") (pinfunction "EP_1") (pintype "input"))
      (node (ref "USB1") (pin "2") (pinfunction "EP_2") (pintype "input"))
      (node (ref "USB1") (pin "3") (pinfunction "EP_3") (pintype "input"))
      (node (ref "USB1") (pin "4") (pinfunction "EP_4") (pintype "input"))
    )
    (net (code "47") (name "Net-(D1-A)") (class "Default")
      (node (ref "D1") (pin "2") (pinfunction "A_2") (pintype "unspecified"))
      (node (ref "L1") (pin "2") (pinfunction "2_2") (pintype "unspecified"))
      (node (ref "U38") (pin "1") (pinfunction "SW_1") (pintype "input"))
    )
    (net (code "48") (name "Net-(D2-K)") (class "Default")
      (node (ref "C21") (pin "2") (pinfunction "2_2") (pintype "input"))
      (node (ref "D2") (pin "1") (pinfunction "K_1") (pintype "input"))
      (node (ref "U9") (pin "20") (pinfunction "VB1_20") (pintype "input"))
    )
    (net (code "49") (name "Net-(D3-K)") (class "Default")
      (node (ref "C22") (pin "2") (pinfunction "2_2") (pintype "input"))
      (node (ref "D3") (pin "1") (pinfunction "K_1") (pintype "input"))
      (node (ref "U9") (pin "17") (pinfunction "VB2_17") (pintype "input"))
    )
    (net (code "50") (name "Net-(D4-K)") (class "Default")
      (node (ref "C23") (pin "2") (pinfunction "2_2") (pintype "input"))
      (node (ref "D4") (pin "1") (pinfunction "K_1") (pintype "input"))
      (node (ref "U9") (pin "14") (pinfunction "VB3_14") (pintype "input"))
    )
    (net (code "51") (name "Net-(D5-A)") (class "Default")
      (node (ref "D5") (pin "2") (pinfunction "A_2") (pintype "input"))
      (node (ref "Q13") (pin "1") (pinfunction "G_1") (pintype "input"))
      (node (ref "R28") (pin "2") (pinfunction "2_2") (pintype "input"))
    )
    (net (code "52") (name "Net-(D6-A)") (class "Default")
      (node (ref "D6") (pin "2") (pinfunction "A_2") (pintype "input"))
      (node (ref "Q14") (pin "1") (pinfunction "G_1") (pintype "input"))
      (node (ref "R5") (pin "2") (pinfunction "2_2") (pintype "input"))
    )
    (net (code "53") (name "Net-(D7-A)") (class "Default")
      (node (ref "D7") (pin "2") (pinfunction "A_2") (pintype "input"))
      (node (ref "Q15") (pin "1") (pinfunction "G_1") (pintype "input"))
      (node (ref "R6") (pin "2") (pinfunction "2_2") (pintype "input"))
    )
    (net (code "54") (name "Net-(D8-A)") (class "Default")
      (node (ref "D8") (pin "2") (pinfunction "A_2") (pintype "input"))
      (node (ref "Q16") (pin "1") (pinfunction "G_1") (pintype "input"))
      (node (ref "R29") (pin "2") (pinfunction "2_2") (pintype "input"))
    )
    (net (code "55") (name "Net-(D9-A)") (class "Default")
      (node (ref "D9") (pin "2") (pinfunction "A_2") (pintype "input"))
      (node (ref "Q17") (pin "1") (pinfunction "G_1") (pintype "input"))
      (node (ref "R30") (pin "2") (pinfunction "2_2") (pintype "input"))
    )
    (net (code "56") (name "Net-(D10-A)") (class "Default")
      (node (ref "D10") (pin "2") (pinfunction "A_2") (pintype "input"))
      (node (ref "Q12") (pin "1") (pinfunction "G_1") (pintype "input"))
      (node (ref "R27") (pin "2") (pinfunction "2_2") (pintype "input"))
    )
    (net (code "57") (name "Net-(D11-K)") (class "Default")
      (node (ref "C30") (pin "2") (pinfunction "2_2") (pintype "input"))
      (node (ref "D11") (pin "1") (pinfunction "K_1") (pintype "input"))
      (node (ref "U13") (pin "20") (pinfunction "VB1_20") (pintype "input"))
    )
    (net (code "58") (name "Net-(D12-K)") (class "Default")
      (node (ref "C31") (pin "2") (pinfunction "2_2") (pintype "input"))
      (node (ref "D12") (pin "1") (pinfunction "K_1") (pintype "input"))
      (node (ref "U13") (pin "17") (pinfunction "VB2_17") (pintype "input"))
    )
    (net (code "59") (name "Net-(D13-K)") (class "Default")
      (node (ref "C32") (pin "2") (pinfunction "2_2") (pintype "input"))
      (node (ref "D13") (pin "1") (pinfunction "K_1") (pintype "input"))
      (node (ref "U13") (pin "14") (pinfunction "VB3_14") (pintype "input"))
    )
    (net (code "60") (name "Net-(D14-A)") (class "Default")
      (node (ref "D14") (pin "2") (pinfunction "A_2") (pintype "input"))
      (node (ref "Q18") (pin "1") (pinfunction "G_1") (pintype "input"))
      (node (ref "R32") (pin "2") (pinfunction "2_2") (pintype "input"))
    )
    (net (code "61") (name "Net-(D15-A)") (class "Default")
      (node (ref "D15") (pin "2") (pinfunction "A_2") (pintype "input"))
      (node (ref "Q19") (pin "1") (pinfunction "G_1") (pintype "input"))
      (node (ref "R33") (pin "2") (pinfunction "2_2") (pintype "input"))
    )
    (net (code "62") (name "Net-(D16-A)") (class "Default")
      (node (ref "D16") (pin "2") (pinfunction "A_2") (pintype "input"))
      (node (ref "Q20") (pin "1") (pinfunction "G_1") (pintype "input"))
      (node (ref "R34") (pin "2") (pinfunction "2_2") (pintype "input"))
    )
    (net (code "63") (name "Net-(D17-A)") (class "Default")
      (node (ref "D17") (pin "2") (pinfunction "A_2") (pintype "input"))
      (node (ref "Q21") (pin "1") (pinfunction "G_1") (pintype "input"))
      (node (ref "R35") (pin "2") (pinfunction "2_2") (pintype "input"))
    )
    (net (code "64") (name "Net-(D18-A)") (class "Default")
      (node (ref "D18") (pin "2") (pinfunction "A_2") (pintype "input"))
      (node (ref "Q22") (pin "1") (pinfunction "G_1") (pintype "input"))
      (node (ref "R36") (pin "2") (pinfunction "2_2") (pintype "input"))
    )
    (net (code "65") (name "Net-(D19-A)") (class "Default")
      (node (ref "D19") (pin "2") (pinfunction "A_2") (pintype "input"))
      (node (ref "Q23") (pin "1") (pinfunction "G_1") (pintype "input"))
      (node (ref "R37") (pin "2") (pinfunction "2_2") (pintype "input"))
    )
    (net (code "66") (name "Net-(LED2-A)") (class "Default")
      (node (ref "LED2") (pin "2") (pinfunction "A_2") (pintype "unspecified"))
      (node (ref "R39") (pin "1") (pinfunction "1_1") (pintype "input"))
    )
    (net (code "67") (name "Net-(LED3-A)") (class "Default")
      (node (ref "LED3") (pin "2") (pinfunction "A_2") (pintype "unspecified"))
      (node (ref "R16") (pin "1") (pinfunction "1_1") (pintype "unspecified"))
    )
    (net (code "68") (name "Net-(LED62-DO)") (class "Default")
      (node (ref "LED62") (pin "4") (pinfunction "DO_4") (pintype "unspecified"))
      (node (ref "LED63") (pin "2") (pinfunction "DI_2") (pintype "unspecified"))
    )
    (net (code "69") (name "Net-(LED63-DO)") (class "Default")
      (node (ref "LED63") (pin "4") (pinfunction "DO_4") (pintype "unspecified"))
      (node (ref "LED64") (pin "2") (pinfunction "DI_2") (pintype "unspecified"))
    )
    (net (code "70") (name "Net-(LED64-DO)") (class "Default")
      (node (ref "LED64") (pin "4") (pinfunction "DO_4") (pintype "unspecified"))
      (node (ref "LED65") (pin "2") (pinfunction "DI_2") (pintype "unspecified"))
    )
    (net (code "71") (name "Net-(LED65-DO)") (class "Default")
      (node (ref "LED65") (pin "4") (pinfunction "DO_4") (pintype "unspecified"))
      (node (ref "LED66") (pin "2") (pinfunction "DI_2") (pintype "unspecified"))
    )
    (net (code "72") (name "Net-(LED66-DO)") (class "Default")
      (node (ref "LED66") (pin "4") (pinfunction "DO_4") (pintype "unspecified"))
      (node (ref "LED67") (pin "2") (pinfunction "DI_2") (pintype "unspecified"))
    )
    (net (code "73") (name "Net-(LED67-DO)") (class "Default")
      (node (ref "LED67") (pin "4") (pinfunction "DO_4") (pintype "unspecified"))
      (node (ref "LED68") (pin "2") (pinfunction "DI_2") (pintype "unspecified"))
    )
    (net (code "74") (name "Net-(LED105-DOUT)") (class "Default")
      (node (ref "LED105") (pin "2") (pinfunction "DOUT_2") (pintype "input"))
      (node (ref "LED106") (pin "4") (pinfunction "DIN_4") (pintype "input"))
    )
    (net (code "75") (name "Net-(LED106-DOUT)") (class "Default")
      (node (ref "LED106") (pin "2") (pinfunction "DOUT_2") (pintype "input"))
      (node (ref "LED107") (pin "4") (pinfunction "DIN_4") (pintype "input"))
    )
    (net (code "76") (name "Net-(LED107-DOUT)") (class "Default")
      (node (ref "LED107") (pin "2") (pinfunction "DOUT_2") (pintype "input"))
      (node (ref "LED108") (pin "4") (pinfunction "DIN_4") (pintype "input"))
    )
    (net (code "77") (name "Net-(LED108-DOUT)") (class "Default")
      (node (ref "LED108") (pin "2") (pinfunction "DOUT_2") (pintype "input"))
      (node (ref "LED109") (pin "4") (pinfunction "DIN_4") (pintype "input"))
    )
    (net (code "78") (name "Net-(LED109-DOUT)") (class "Default")
      (node (ref "LED109") (pin "2") (pinfunction "DOUT_2") (pintype "input"))
      (node (ref "LED110") (pin "4") (pinfunction "DIN_4") (pintype "input"))
    )
    (net (code "79") (name "Net-(LED110-DOUT)") (class "Default")
      (node (ref "LED110") (pin "2") (pinfunction "DOUT_2") (pintype "input"))
      (node (ref "LED111") (pin "4") (pinfunction "DIN_4") (pintype "input"))
    )
    (net (code "80") (name "Net-(LED111-DOUT)") (class "Default")
      (node (ref "LED111") (pin "2") (pinfunction "DOUT_2") (pintype "input"))
      (node (ref "LED112") (pin "4") (pinfunction "DIN_4") (pintype "input"))
    )
    (net (code "81") (name "Net-(LED112-DOUT)") (class "Default")
      (node (ref "LED112") (pin "2") (pinfunction "DOUT_2") (pintype "input"))
      (node (ref "LED113") (pin "4") (pinfunction "DIN_4") (pintype "input"))
    )
    (net (code "82") (name "Net-(LED113-DOUT)") (class "Default")
      (node (ref "LED113") (pin "2") (pinfunction "DOUT_2") (pintype "input"))
      (node (ref "LED114") (pin "4") (pinfunction "DIN_4") (pintype "input"))
    )
    (net (code "83") (name "Net-(LED114-DOUT)") (class "Default")
      (node (ref "LED114") (pin "2") (pinfunction "DOUT_2") (pintype "input"))
      (node (ref "LED115") (pin "4") (pinfunction "DIN_4") (pintype "input"))
    )
    (net (code "84") (name "Net-(LED115-DOUT)") (class "Default")
      (node (ref "LED115") (pin "2") (pinfunction "DOUT_2") (pintype "input"))
      (node (ref "LED116") (pin "4") (pinfunction "DIN_4") (pintype "input"))
    )
    (net (code "85") (name "Net-(LED116-DOUT)") (class "Default")
      (node (ref "LED116") (pin "2") (pinfunction "DOUT_2") (pintype "input"))
      (node (ref "LED117") (pin "4") (pinfunction "DIN_4") (pintype "input"))
    )
    (net (code "86") (name "Net-(LED117-DOUT)") (class "Default")
      (node (ref "LED117") (pin "2") (pinfunction "DOUT_2") (pintype "input"))
      (node (ref "LED118") (pin "4") (pinfunction "DIN_4") (pintype "input"))
    )
    (net (code "87") (name "Net-(LED118-DOUT)") (class "Default")
      (node (ref "LED118") (pin "2") (pinfunction "DOUT_2") (pintype "input"))
      (node (ref "LED119") (pin "4") (pinfunction "DIN_4") (pintype "input"))
    )
    (net (code "88") (name "Net-(LED119-DOUT)") (class "Default")
      (node (ref "LED119") (pin "2") (pinfunction "DOUT_2") (pintype "input"))
      (node (ref "LED120") (pin "4") (pinfunction "DIN_4") (pintype "input"))
    )
    (net (code "89") (name "Net-(LED120-DOUT)") (class "Default")
      (node (ref "LED120") (pin "2") (pinfunction "DOUT_2") (pintype "input"))
      (node (ref "LED121") (pin "4") (pinfunction "DIN_4") (pintype "input"))
    )
    (net (code "90") (name "Net-(LED121-DOUT)") (class "Default")
      (node (ref "LED121") (pin "2") (pinfunction "DOUT_2") (pintype "input"))
      (node (ref "LED122") (pin "4") (pinfunction "DIN_4") (pintype "input"))
    )
    (net (code "91") (name "Net-(LED122-DOUT)") (class "Default")
      (node (ref "LED122") (pin "2") (pinfunction "DOUT_2") (pintype "input"))
      (node (ref "LED123") (pin "4") (pinfunction "DIN_4") (pintype "input"))
    )
    (net (code "92") (name "Net-(LED123-DOUT)") (class "Default")
      (node (ref "LED123") (pin "2") (pinfunction "DOUT_2") (pintype "input"))
      (node (ref "LED124") (pin "4") (pinfunction "DIN_4") (pintype "input"))
    )
    (net (code "93") (name "Net-(LED124-DOUT)") (class "Default")
      (node (ref "LED124") (pin "2") (pinfunction "DOUT_2") (pintype "input"))
      (node (ref "LED125") (pin "4") (pinfunction "DIN_4") (pintype "input"))
    )
    (net (code "94") (name "Net-(LED125-DOUT)") (class "Default")
      (node (ref "LED125") (pin "2") (pinfunction "DOUT_2") (pintype "input"))
      (node (ref "LED126") (pin "4") (pinfunction "DIN_4") (pintype "input"))
    )
    (net (code "95") (name "Net-(LED126-DOUT)") (class "Default")
      (node (ref "LED126") (pin "2") (pinfunction "DOUT_2") (pintype "input"))
      (node (ref "LED127") (pin "4") (pinfunction "DIN_4") (pintype "input"))
    )
    (net (code "96") (name "Net-(LED127-DOUT)") (class "Default")
      (node (ref "LED127") (pin "2") (pinfunction "DOUT_2") (pintype "input"))
      (node (ref "LED128") (pin "4") (pinfunction "DIN_4") (pintype "input"))
    )
    (net (code "97") (name "Net-(LED128-DOUT)") (class "Default")
      (node (ref "LED128") (pin "2") (pinfunction "DOUT_2") (pintype "input"))
      (node (ref "LED129") (pin "4") (pinfunction "DIN_4") (pintype "input"))
    )
    (net (code "98") (name "Net-(LED129-DOUT)") (class "Default")
      (node (ref "LED129") (pin "2") (pinfunction "DOUT_2") (pintype "input"))
      (node (ref "LED130") (pin "4") (pinfunction "DIN_4") (pintype "input"))
    )
    (net (code "99") (name "Net-(LED130-DOUT)") (class "Default")
      (node (ref "LED130") (pin "2") (pinfunction "DOUT_2") (pintype "input"))
      (node (ref "LED131") (pin "4") (pinfunction "DIN_4") (pintype "input"))
    )
    (net (code "100") (name "Net-(LED131-DOUT)") (class "Default")
      (node (ref "LED131") (pin "2") (pinfunction "DOUT_2") (pintype "input"))
      (node (ref "LED132") (pin "4") (pinfunction "DIN_4") (pintype "input"))
    )
    (net (code "101") (name "Net-(LED132-DOUT)") (class "Default")
      (node (ref "LED132") (pin "2") (pinfunction "DOUT_2") (pintype "input"))
      (node (ref "LED133") (pin "4") (pinfunction "DIN_4") (pintype "input"))
    )
    (net (code "102") (name "Net-(LED133-DOUT)") (class "Default")
      (node (ref "LED133") (pin "2") (pinfunction "DOUT_2") (pintype "input"))
      (node (ref "LED134") (pin "4") (pinfunction "DIN_4") (pintype "input"))
    )
    (net (code "103") (name "Net-(LED134-DOUT)") (class "Default")
      (node (ref "LED134") (pin "2") (pinfunction "DOUT_2") (pintype "input"))
      (node (ref "LED135") (pin "4") (pinfunction "DIN_4") (pintype "input"))
    )
    (net (code "104") (name "Net-(LED135-DOUT)") (class "Default")
      (node (ref "LED135") (pin "2") (pinfunction "DOUT_2") (pintype "input"))
      (node (ref "LED136") (pin "4") (pinfunction "DIN_4") (pintype "input"))
    )
    (net (code "105") (name "Net-(LED136-DOUT)") (class "Default")
      (node (ref "LED136") (pin "2") (pinfunction "DOUT_2") (pintype "input"))
      (node (ref "LED137") (pin "4") (pinfunction "DIN_4") (pintype "input"))
    )
    (net (code "106") (name "Net-(LED137-DOUT)") (class "Default")
      (node (ref "LED137") (pin "2") (pinfunction "DOUT_2") (pintype "input"))
      (node (ref "LED138") (pin "4") (pinfunction "DIN_4") (pintype "input"))
    )
    (net (code "107") (name "Net-(LED138-DOUT)") (class "Default")
      (node (ref "LED138") (pin "2") (pinfunction "DOUT_2") (pintype "input"))
      (node (ref "LED139") (pin "4") (pinfunction "DIN_4") (pintype "input"))
    )
    (net (code "108") (name "Net-(LED139-DOUT)") (class "Default")
      (node (ref "LED139") (pin "2") (pinfunction "DOUT_2") (pintype "input"))
      (node (ref "LED140") (pin "4") (pinfunction "DIN_4") (pintype "input"))
    )
    (net (code "109") (name "Net-(LED140-DOUT)") (class "Default")
      (node (ref "LED140") (pin "2") (pinfunction "DOUT_2") (pintype "input"))
      (node (ref "LED141") (pin "4") (pinfunction "DIN_4") (pintype "input"))
    )
    (net (code "110") (name "Net-(LED141-DOUT)") (class "Default")
      (node (ref "LED141") (pin "2") (pinfunction "DOUT_2") (pintype "input"))
      (node (ref "LED142") (pin "4") (pinfunction "DIN_4") (pintype "input"))
    )
    (net (code "111") (name "Net-(LED142-DOUT)") (class "Default")
      (node (ref "LED142") (pin "2") (pinfunction "DOUT_2") (pintype "input"))
      (node (ref "LED143") (pin "4") (pinfunction "DIN_4") (pintype "input"))
    )
    (net (code "112") (name "Net-(LED143-DOUT)") (class "Default")
      (node (ref "LED143") (pin "2") (pinfunction "DOUT_2") (pintype "input"))
      (node (ref "LED144") (pin "4") (pinfunction "DIN_4") (pintype "input"))
    )
    (net (code "113") (name "Net-(LED144-DOUT)") (class "Default")
      (node (ref "LED144") (pin "2") (pinfunction "DOUT_2") (pintype "input"))
      (node (ref "LED145") (pin "4") (pinfunction "DIN_4") (pintype "input"))
    )
    (net (code "114") (name "Net-(LED145-DOUT)") (class "Default")
      (node (ref "LED145") (pin "2") (pinfunction "DOUT_2") (pintype "input"))
      (node (ref "LED146") (pin "4") (pinfunction "DIN_4") (pintype "input"))
    )
    (net (code "115") (name "Net-(LED146-DOUT)") (class "Default")
      (node (ref "LED146") (pin "2") (pinfunction "DOUT_2") (pintype "input"))
      (node (ref "LED147") (pin "4") (pinfunction "DIN_4") (pintype "input"))
    )
    (net (code "116") (name "Net-(LED147-DOUT)") (class "Default")
      (node (ref "LED147") (pin "2") (pinfunction "DOUT_2") (pintype "input"))
      (node (ref "LED148") (pin "4") (pinfunction "DIN_4") (pintype "input"))
    )
    (net (code "117") (name "Net-(U8-CTS#)") (class "Default")
      (node (ref "R25") (pin "1") (pinfunction "1_1") (pintype "input"))
      (node (ref "U8") (pin "5") (pinfunction "CTS#_5") (pintype "unspecified"))
    )
    (net (code "118") (name "Net-(U11-RESET#)") (class "Default")
      (node (ref "C24") (pin "1") (pinfunction "1_1") (pintype "input"))
      (node (ref "R31") (pin "1") (pinfunction "1_1") (pintype "input"))
      (node (ref "U11") (pin "3") (pinfunction "RESET#_3") (pintype "unspecified"))
    )
    (net (code "119") (name "Net-(U38-FB)") (class "Default")
      (node (ref "R3") (pin "2") (pinfunction "2_2") (pintype "unspecified"))
      (node (ref "R38") (pin "1") (pinfunction "1_1") (pintype "unspecified"))
      (node (ref "U38") (pin "3") (pinfunction "FB_3") (pintype "input"))
    )
    (net (code "120") (name "Net-(USB1-CC1)") (class "Default")
      (node (ref "R61") (pin "2") (pinfunction "2_2") (pintype "input"))
      (node (ref "USB1") (pin "A5") (pinfunction "CC1_A5") (pintype "input"))
    )
    (net (code "121") (name "Net-(USB1-CC2)") (class "Default")
      (node (ref "R62") (pin "1") (pinfunction "1_1") (pintype "input"))
      (node (ref "USB1") (pin "B5") (pinfunction "CC2_B5") (pintype "input"))
    )
    (net (code "122") (name "RGB_IN") (class "Default")
      (node (ref "LED105") (pin "4") (pinfunction "DIN_4") (pintype "input"))
      (node (ref "U1") (pin "31") (pinfunction "IO38_31") (pintype "input"))
    )
    (net (code "123") (name "RXD0") (class "Default")
      (node (ref "U1") (pin "36") (pinfunction "RXD0_36") (pintype "input"))
      (node (ref "U8") (pin "8") (pinfunction "TXD_8") (pintype "unspecified"))
    )
    (net (code "124") (name "SCL") (class "Default")
      (node (ref "U1") (pin "38") (pinfunction "IO2_38") (pintype "input"))
      (node (ref "U11") (pin "12") (pinfunction "SCL_12") (pintype "unspecified"))
    )
    (net (code "125") (name "SCL_0") (class "Default")
      (node (ref "U10") (pin "7") (pinfunction "B_7") (pintype "input"))
      (node (ref "U11") (pin "6") (pinfunction "SC0_6") (pintype "unspecified"))
    )
    (net (code "126") (name "SCL_1") (class "Default")
      (node (ref "U11") (pin "10") (pinfunction "SC1_10") (pintype "unspecified"))
      (node (ref "U12") (pin "7") (pinfunction "B_7") (pintype "input"))
    )
    (net (code "127") (name "SDA") (class "Default")
      (node (ref "U1") (pin "39") (pinfunction "IO1_39") (pintype "input"))
      (node (ref "U11") (pin "13") (pinfunction "SDA_13") (pintype "unspecified"))
    )
    (net (code "128") (name "SDA_0") (class "Default")
      (node (ref "U10") (pin "6") (pinfunction "A_6") (pintype "input"))
      (node (ref "U11") (pin "5") (pinfunction "SD0_5") (pintype "unspecified"))
    )
    (net (code "129") (name "SDA_1") (class "Default")
      (node (ref "U11") (pin "9") (pinfunction "SD1_9") (pintype "unspecified"))
      (node (ref "U12") (pin "6") (pinfunction "A_6") (pintype "input"))
    )
    (net (code "130") (name "SEL1") (class "Default")
      (node (ref "U1") (pin "33") (pinfunction "IO40_33") (pintype "input"))
      (node (ref "U31") (pin "9") (pinfunction "B_9") (pintype "input"))
    )
    (net (code "131") (name "SEL2") (class "Default")
      (node (ref "U1") (pin "34") (pinfunction "IO41_34") (pintype "input"))
      (node (ref "U31") (pin "10") (pinfunction "A_10") (pintype "input"))
    )
    (net (code "132") (name "START") (class "Default")
      (node (ref "C50") (pin "2") (pinfunction "2_2") (pintype "unspecified"))
      (node (ref "U30") (pin "3") (pinfunction "VOUT_3") (pintype "unspecified"))
      (node (ref "U31") (pin "15") (pinfunction "X2_15") (pintype "input"))
    )
    (net (code "133") (name "TXD0") (class "Default")
      (node (ref "U1") (pin "37") (pinfunction "TXD0_37") (pintype "input"))
      (node (ref "U8") (pin "9") (pinfunction "RXD_9") (pintype "unspecified"))
    )
    (net (code "134") (name "VS1_0") (class "Default")
      (node (ref "C21") (pin "1") (pinfunction "1_1") (pintype "input"))
      (node (ref "CN3") (pin "1") (pinfunction "1_1") (pintype "input"))
      (node (ref "Q12") (pin "2") (pinfunction "S_2") (pintype "input"))
      (node (ref "Q13") (pin "3") (pinfunction "D_3") (pintype "input"))
      (node (ref "U9") (pin "18") (pinfunction "VS1_18") (pintype "input"))
    )
    (net (code "135") (name "VS1_1") (class "Default")
      (node (ref "C30") (pin "1") (pinfunction "1_1") (pintype "input"))
      (node (ref "CN4") (pin "1") (pinfunction "1_1") (pintype "input"))
      (node (ref "Q18") (pin "2") (pinfunction "S_2") (pintype "input"))
      (node (ref "Q19") (pin "3") (pinfunction "D_3") (pintype "input"))
      (node (ref "U13") (pin "18") (pinfunction "VS1_18") (pintype "input"))
    )
    (net (code "136") (name "VS2_0") (class "Default")
      (node (ref "C22") (pin "1") (pinfunction "1_1") (pintype "input"))
      (node (ref "CN3") (pin "2") (pinfunction "2_2") (pintype "input"))
      (node (ref "Q14") (pin "2") (pinfunction "S_2") (pintype "input"))
      (node (ref "Q15") (pin "3") (pinfunction "D_3") (pintype "input"))
      (node (ref "U9") (pin "15") (pinfunction "VS2_15") (pintype "input"))
    )
    (net (code "137") (name "VS2_1") (class "Default")
      (node (ref "C31") (pin "1") (pinfunction "1_1") (pintype "input"))
      (node (ref "CN4") (pin "2") (pinfunction "2_2") (pintype "input"))
      (node (ref "Q20") (pin "2") (pinfunction "S_2") (pintype "input"))
      (node (ref "Q21") (pin "3") (pinfunction "D_3") (pintype "input"))
      (node (ref "U13") (pin "15") (pinfunction "VS2_15") (pintype "input"))
    )
    (net (code "138") (name "VS3_0") (class "Default")
      (node (ref "C23") (pin "1") (pinfunction "1_1") (pintype "input"))
      (node (ref "CN3") (pin "3") (pinfunction "3_3") (pintype "input"))
      (node (ref "Q16") (pin "2") (pinfunction "S_2") (pintype "input"))
      (node (ref "Q17") (pin "3") (pinfunction "D_3") (pintype "input"))
      (node (ref "U9") (pin "12") (pinfunction "VS3_12") (pintype "input"))
    )
    (net (code "139") (name "VS3_1") (class "Default")
      (node (ref "C32") (pin "1") (pinfunction "1_1") (pintype "input"))
      (node (ref "CN4") (pin "3") (pinfunction "3_3") (pintype "input"))
      (node (ref "Q22") (pin "2") (pinfunction "S_2") (pintype "input"))
      (node (ref "Q23") (pin "3") (pinfunction "D_3") (pintype "input"))
      (node (ref "U13") (pin "12") (pinfunction "VS3_12") (pintype "input"))
    )
    (net (code "140") (name "unconnected-(LED68-DO-Pad4)") (class "Default")
      (node (ref "LED68") (pin "4") (pinfunction "DO_4") (pintype "unspecified+no_connect"))
    )
    (net (code "141") (name "unconnected-(U1-IO3-Pad15)") (class "Default")
      (node (ref "U1") (pin "15") (pinfunction "IO3_15") (pintype "input"))
    )
    (net (code "142") (name "unconnected-(U1-IO4-Pad4)") (class "Default")
      (node (ref "U1") (pin "4") (pinfunction "IO4_4") (pintype "input"))
    )
    (net (code "143") (name "unconnected-(U1-IO5-Pad5)") (class "Default")
      (node (ref "U1") (pin "5") (pinfunction "IO5_5") (pintype "input"))
    )
    (net (code "144") (name "unconnected-(U1-IO6-Pad6)") (class "Default")
      (node (ref "U1") (pin "6") (pinfunction "IO6_6") (pintype "input"))
    )
    (net (code "145") (name "unconnected-(U1-IO7-Pad7)") (class "Default")
      (node (ref "U1") (pin "7") (pinfunction "IO7_7") (pintype "input"))
    )
    (net (code "146") (name "unconnected-(U1-IO9-Pad17)") (class "Default")
      (node (ref "U1") (pin "17") (pinfunction "IO9_17") (pintype "input"))
    )
    (net (code "147") (name "unconnected-(U1-IO14-Pad22)") (class "Default")
      (node (ref "U1") (pin "22") (pinfunction "IO14_22") (pintype "input"))
    )
    (net (code "148") (name "unconnected-(U1-IO19-Pad13)") (class "Default")
      (node (ref "U1") (pin "13") (pinfunction "IO19_13") (pintype "input"))
    )
    (net (code "149") (name "unconnected-(U1-IO20-Pad14)") (class "Default")
      (node (ref "U1") (pin "14") (pinfunction "IO20_14") (pintype "input"))
    )
    (net (code "150") (name "unconnected-(U1-IO21-Pad23)") (class "Default")
      (node (ref "U1") (pin "23") (pinfunction "IO21_23") (pintype "input"))
    )
    (net (code "151") (name "unconnected-(U1-IO35-Pad28)") (class "Default")
      (node (ref "U1") (pin "28") (pinfunction "IO35_28") (pintype "input"))
    )
    (net (code "152") (name "unconnected-(U1-IO36-Pad29)") (class "Default")
      (node (ref "U1") (pin "29") (pinfunction "IO36_29") (pintype "input"))
    )
    (net (code "153") (name "unconnected-(U1-IO37-Pad30)") (class "Default")
      (node (ref "U1") (pin "30") (pinfunction "IO37_30") (pintype "input"))
    )
    (net (code "154") (name "unconnected-(U1-IO39-Pad32)") (class "Default")
      (node (ref "U1") (pin "32") (pinfunction "IO39_32") (pintype "input"))
    )
    (net (code "155") (name "unconnected-(U1-IO42-Pad35)") (class "Default")
      (node (ref "U1") (pin "35") (pinfunction "IO42_35") (pintype "input"))
    )
    (net (code "156") (name "unconnected-(U1-IO45-Pad26)") (class "Default")
      (node (ref "U1") (pin "26") (pinfunction "IO45_26") (pintype "input"))
    )
    (net (code "157") (name "unconnected-(U1-IO46-Pad16)") (class "Default")
      (node (ref "U1") (pin "16") (pinfunction "IO46_16") (pintype "input"))
    )
    (net (code "158") (name "unconnected-(U1-IO47-Pad24)") (class "Default")
      (node (ref "U1") (pin "24") (pinfunction "IO47_24") (pintype "input"))
    )
    (net (code "159") (name "unconnected-(U1-IO48-Pad25)") (class "Default")
      (node (ref "U1") (pin "25") (pinfunction "IO48_25") (pintype "input"))
    )
    (net (code "160") (name "unconnected-(U10-OUT-Pad3)") (class "Default")
      (node (ref "U10") (pin "3") (pinfunction "OUT_3") (pintype "input+no_connect"))
    )
    (net (code "161") (name "unconnected-(U10-PUSH-Pad5)") (class "Default")
      (node (ref "U10") (pin "5") (pinfunction "PUSH_5") (pintype "input+no_connect"))
    )
    (net (code "162") (name "unconnected-(U11-INT#-Pad11)") (class "Default")
      (node (ref "U11") (pin "11") (pinfunction "INT#_11") (pintype "unspecified+no_connect"))
    )
    (net (code "163") (name "unconnected-(U11-INT0#-Pad4)") (class "Default")
      (node (ref "U11") (pin "4") (pinfunction "INT0#_4") (pintype "unspecified+no_connect"))
    )
    (net (code "164") (name "unconnected-(U11-INT1#-Pad8)") (class "Default")
      (node (ref "U11") (pin "8") (pinfunction "INT1#_8") (pintype "unspecified+no_connect"))
    )
    (net (code "165") (name "unconnected-(U12-OUT-Pad3)") (class "Default")
      (node (ref "U12") (pin "3") (pinfunction "OUT_3") (pintype "input+no_connect"))
    )
    (net (code "166") (name "unconnected-(U12-PUSH-Pad5)") (class "Default")
      (node (ref "U12") (pin "5") (pinfunction "PUSH_5") (pintype "input+no_connect"))
    )
    (net (code "167") (name "unconnected-(U31-NC-Pad7)") (class "Default")
      (node (ref "U31") (pin "7") (pinfunction "NC_7") (pintype "input+no_connect"))
    )
    (net (code "168") (name "unconnected-(U31-X3-Pad11)") (class "Default")
      (node (ref "U31") (pin "11") (pinfunction "X3_11") (pintype "input+no_connect"))
    )
    (net (code "169") (name "unconnected-(U38-NC-Pad6)") (class "Default")
      (node (ref "U38") (pin "6") (pinfunction "NC_6") (pintype "input"))
    )
    (net (code "170") (name "unconnected-(USB1-SUB1-PadA8)") (class "Default")
      (node (ref "USB1") (pin "A8") (pinfunction "SUB1_A8") (pintype "input+no_connect"))
    )
    (net (code "171") (name "unconnected-(USB1-SUB2-PadB8)") (class "Default")
      (node (ref "USB1") (pin "B8") (pinfunction "SUB2_B8") (pintype "input+no_connect"))
    )
  )
)
